# cpu-68010.net
KiCad netlist of a schematic drawn in EAGLE
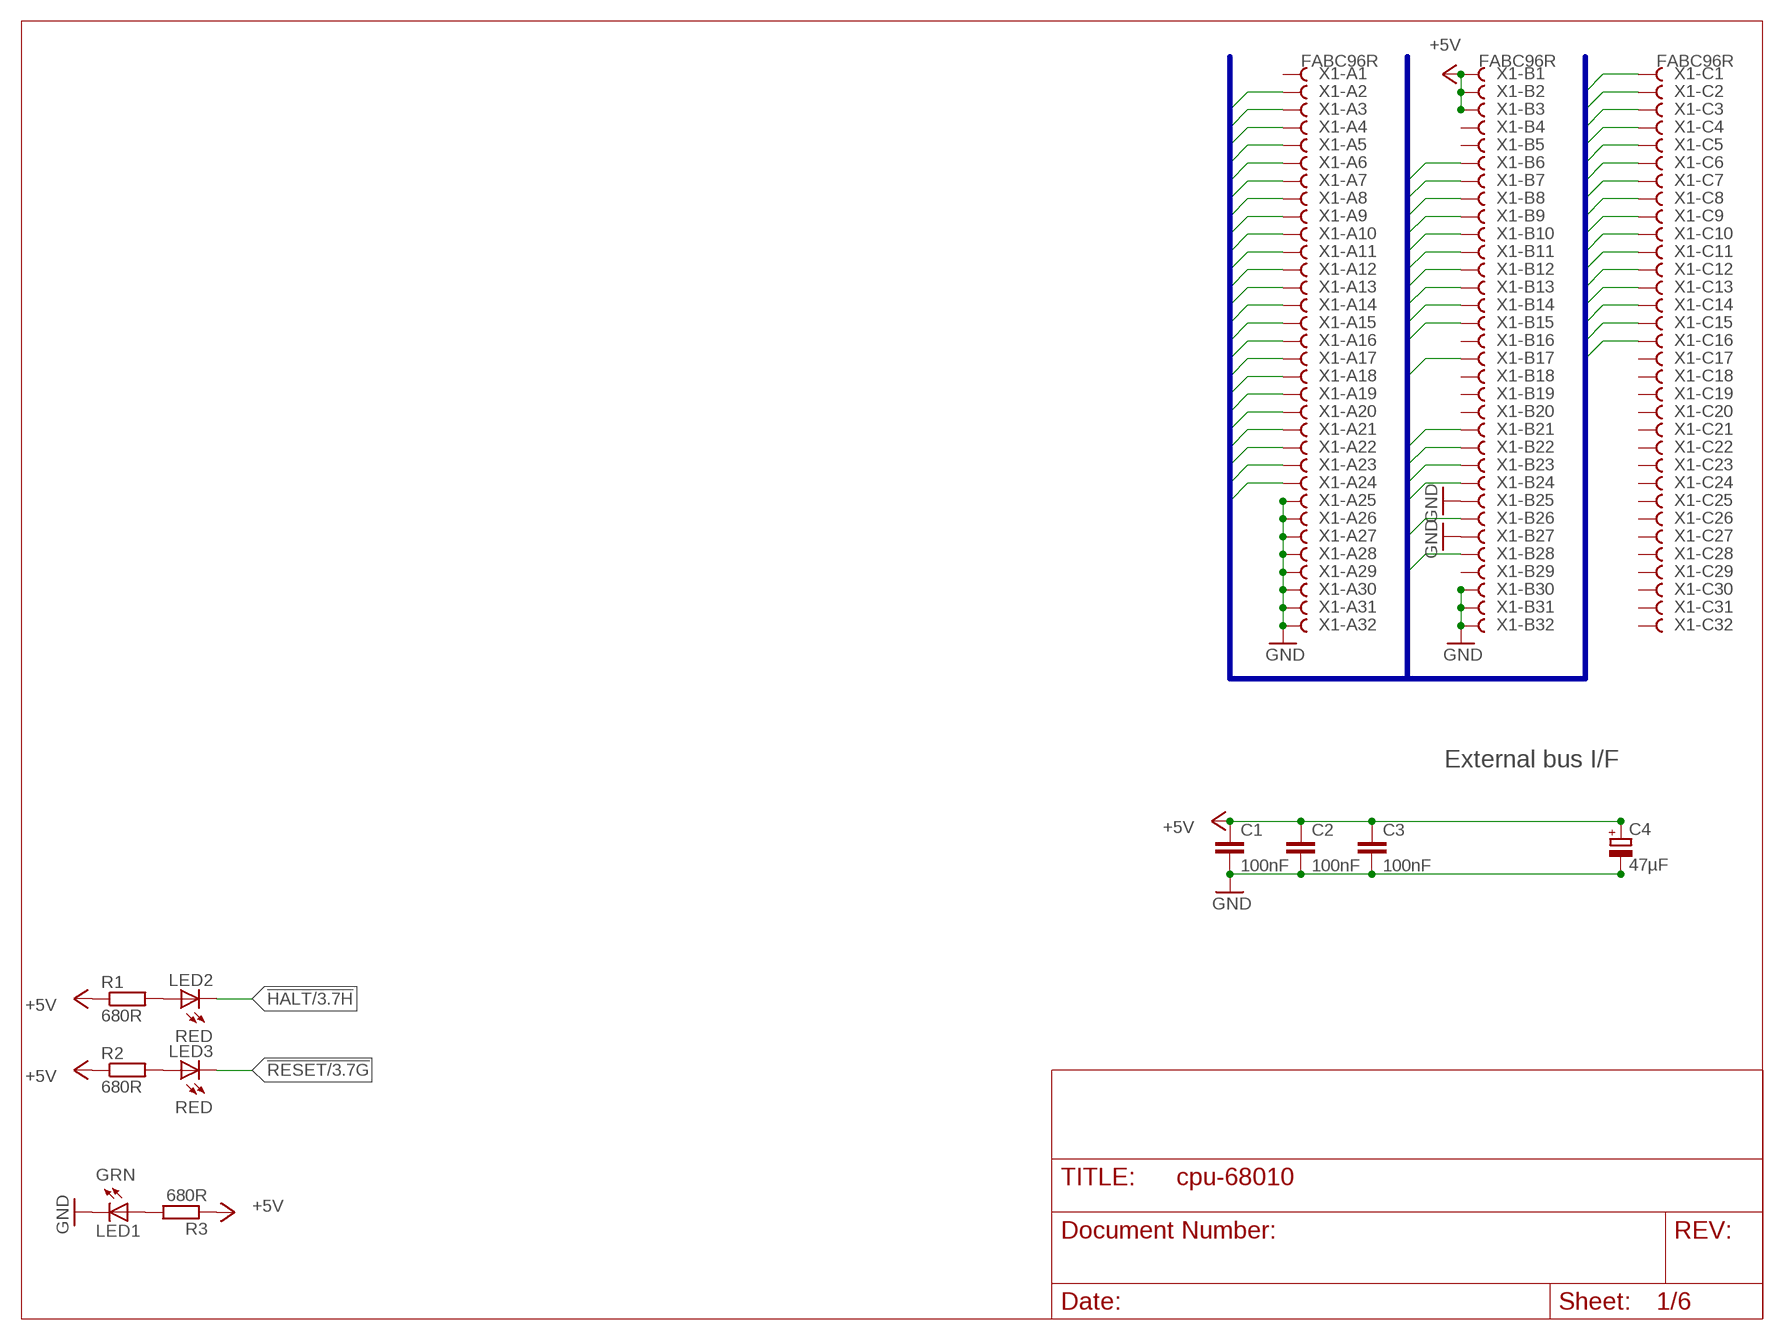
[diagram p0: schematic, sheet 1]
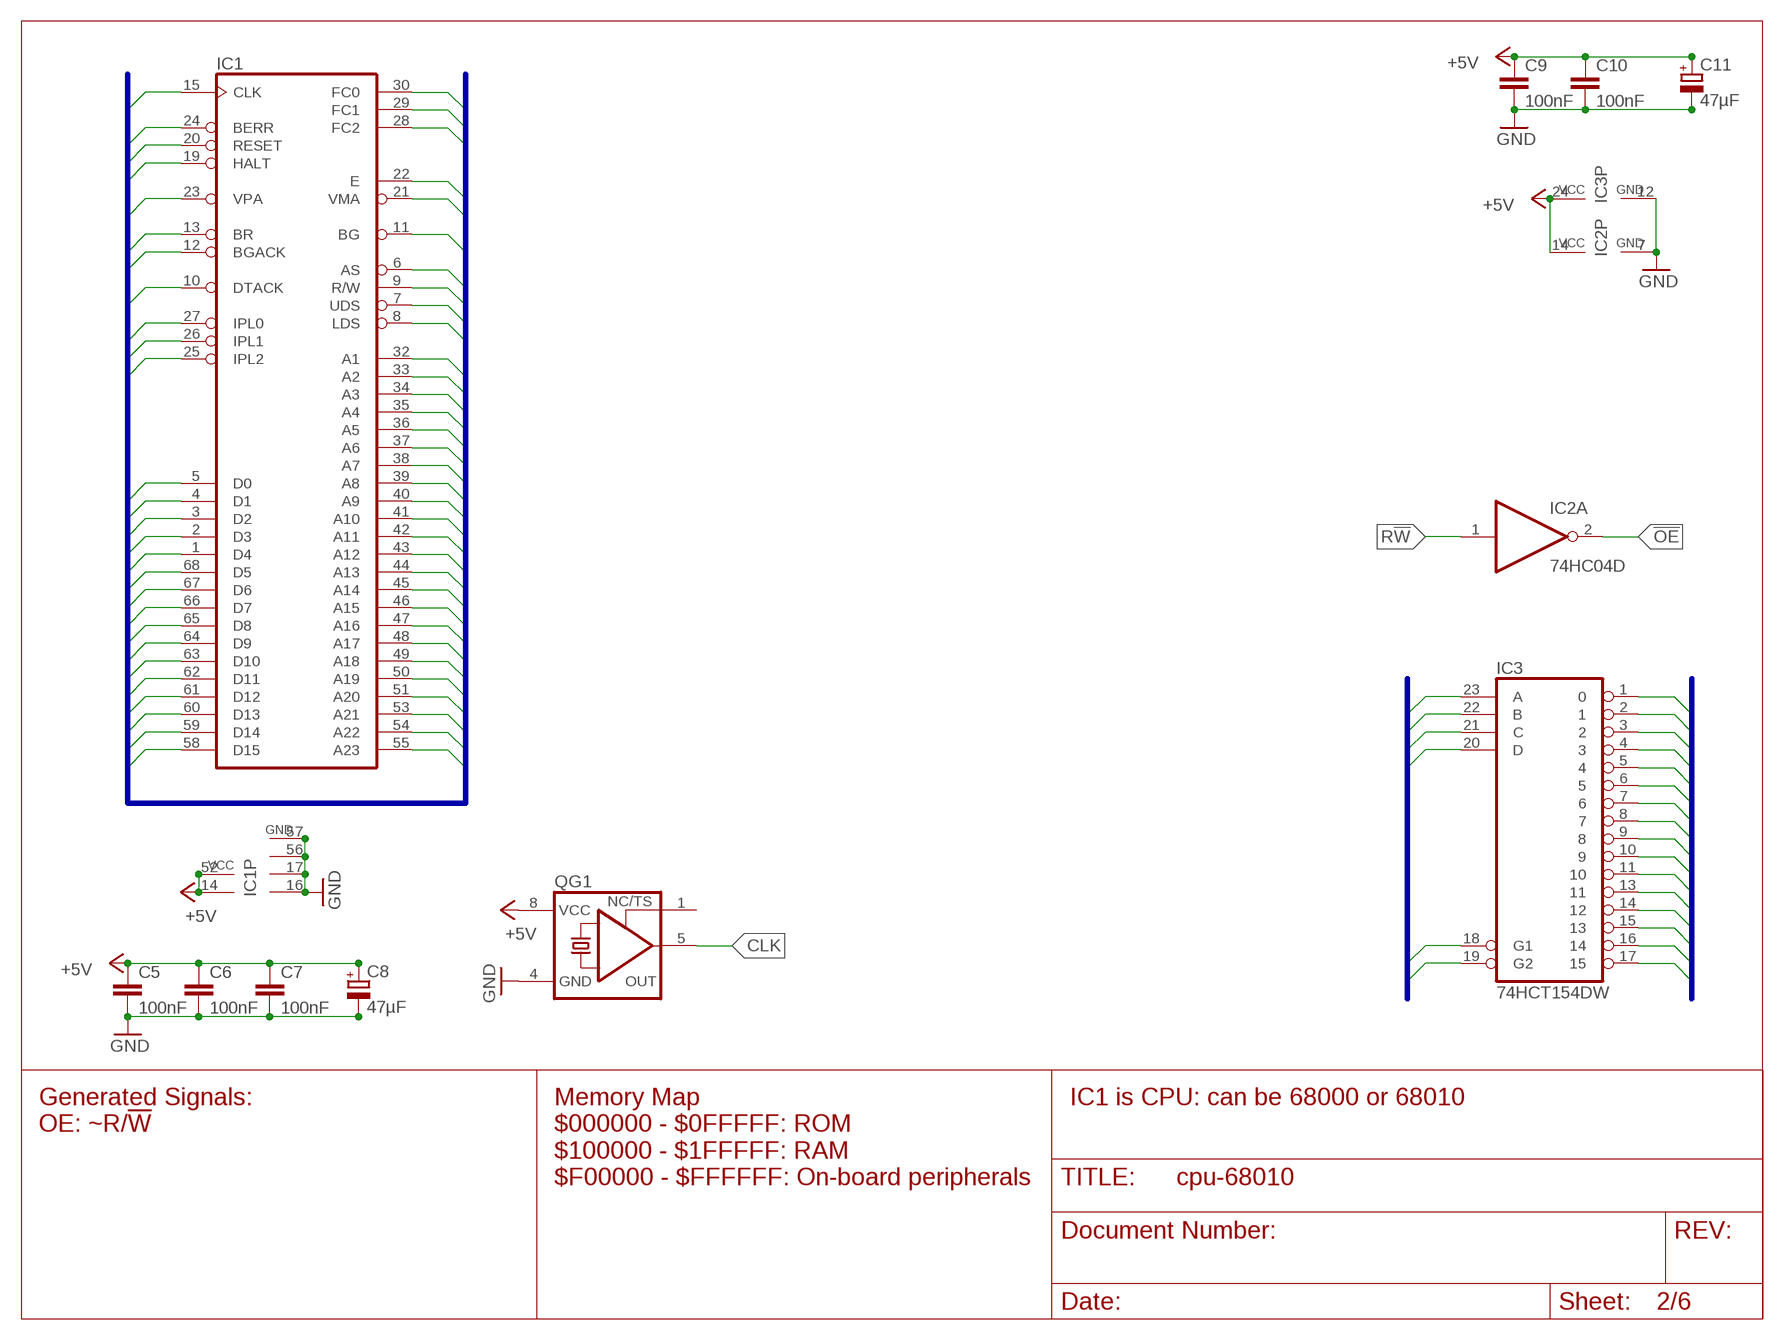
[diagram p1: schematic, sheet 2]
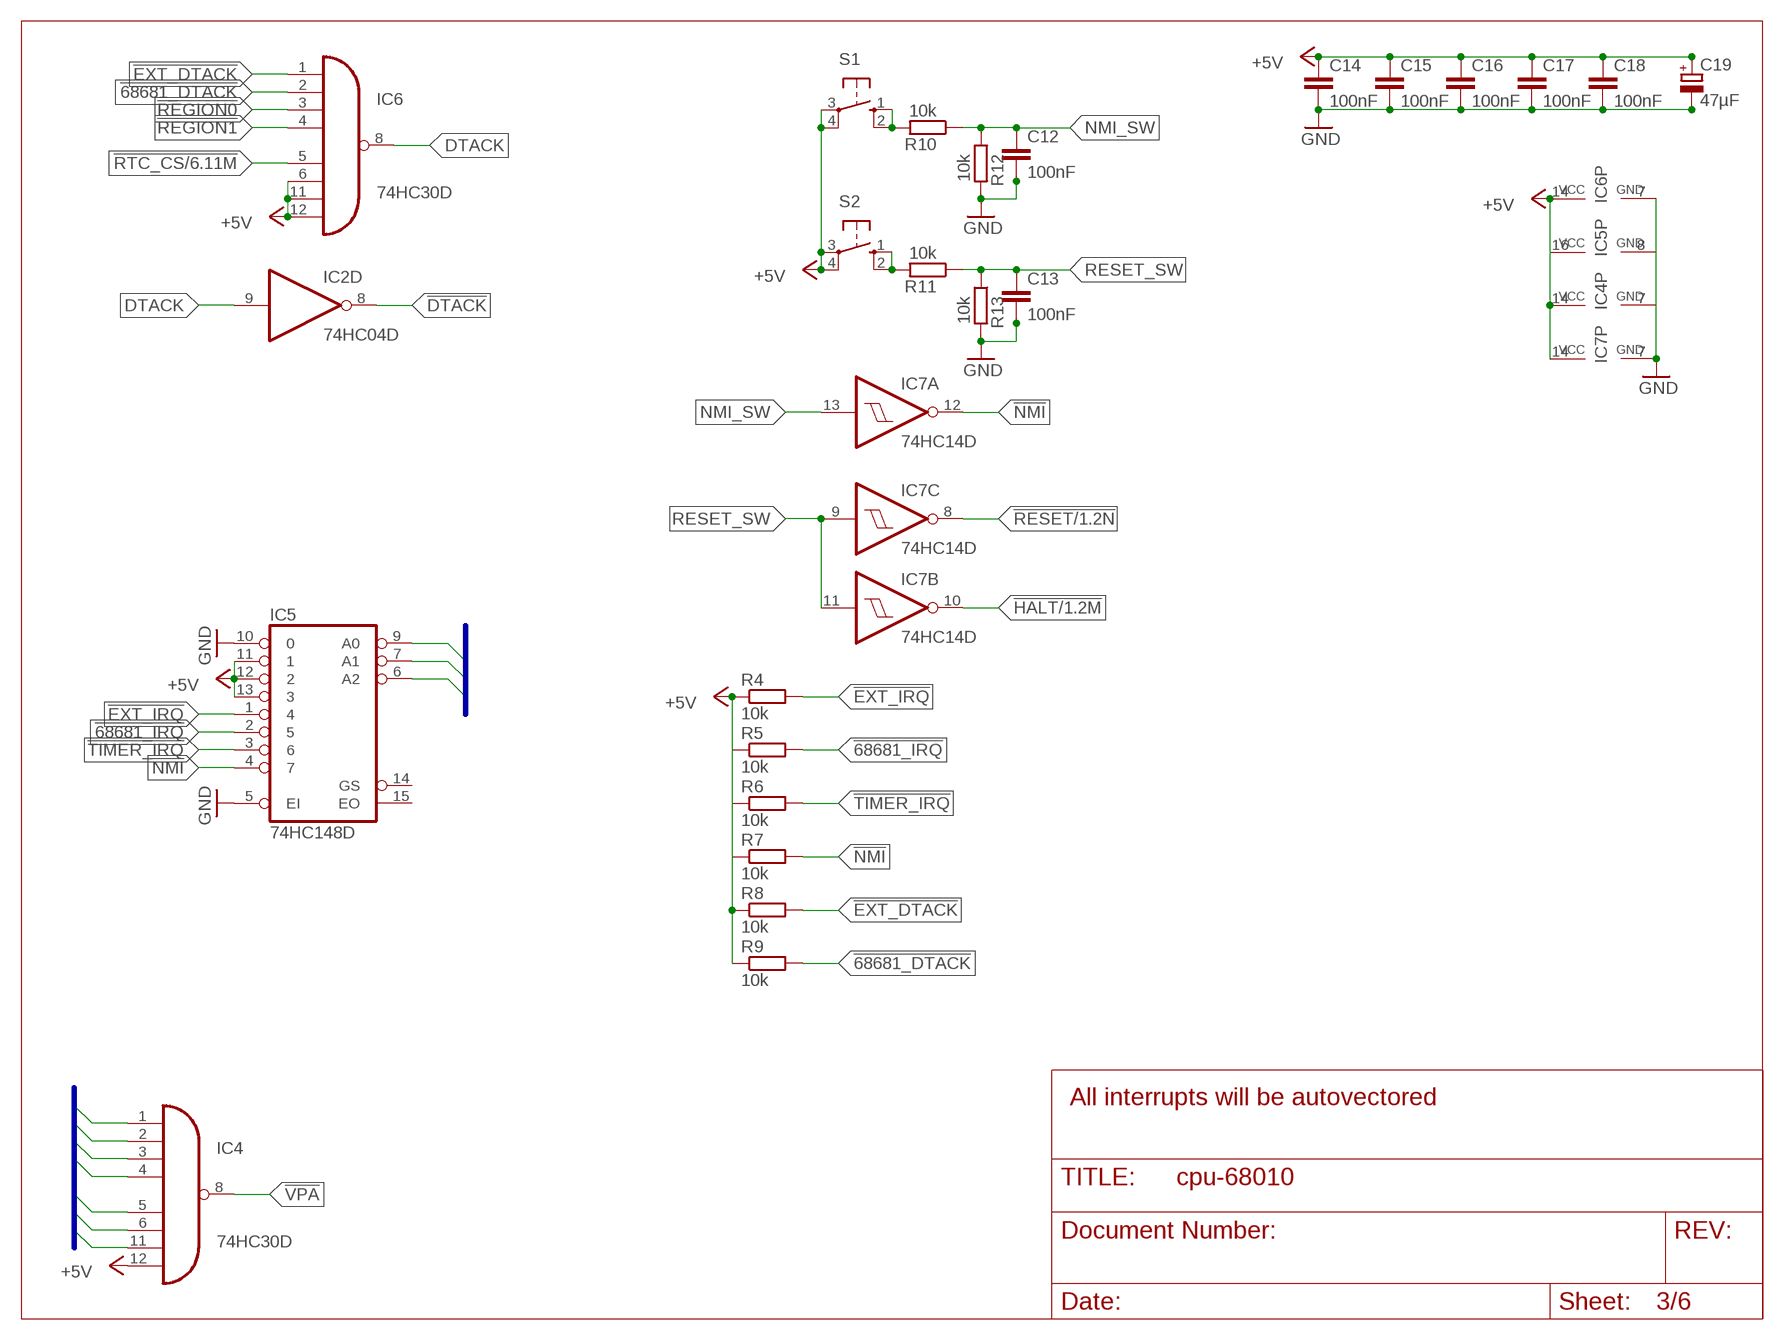
[diagram p2: schematic, sheet 3]
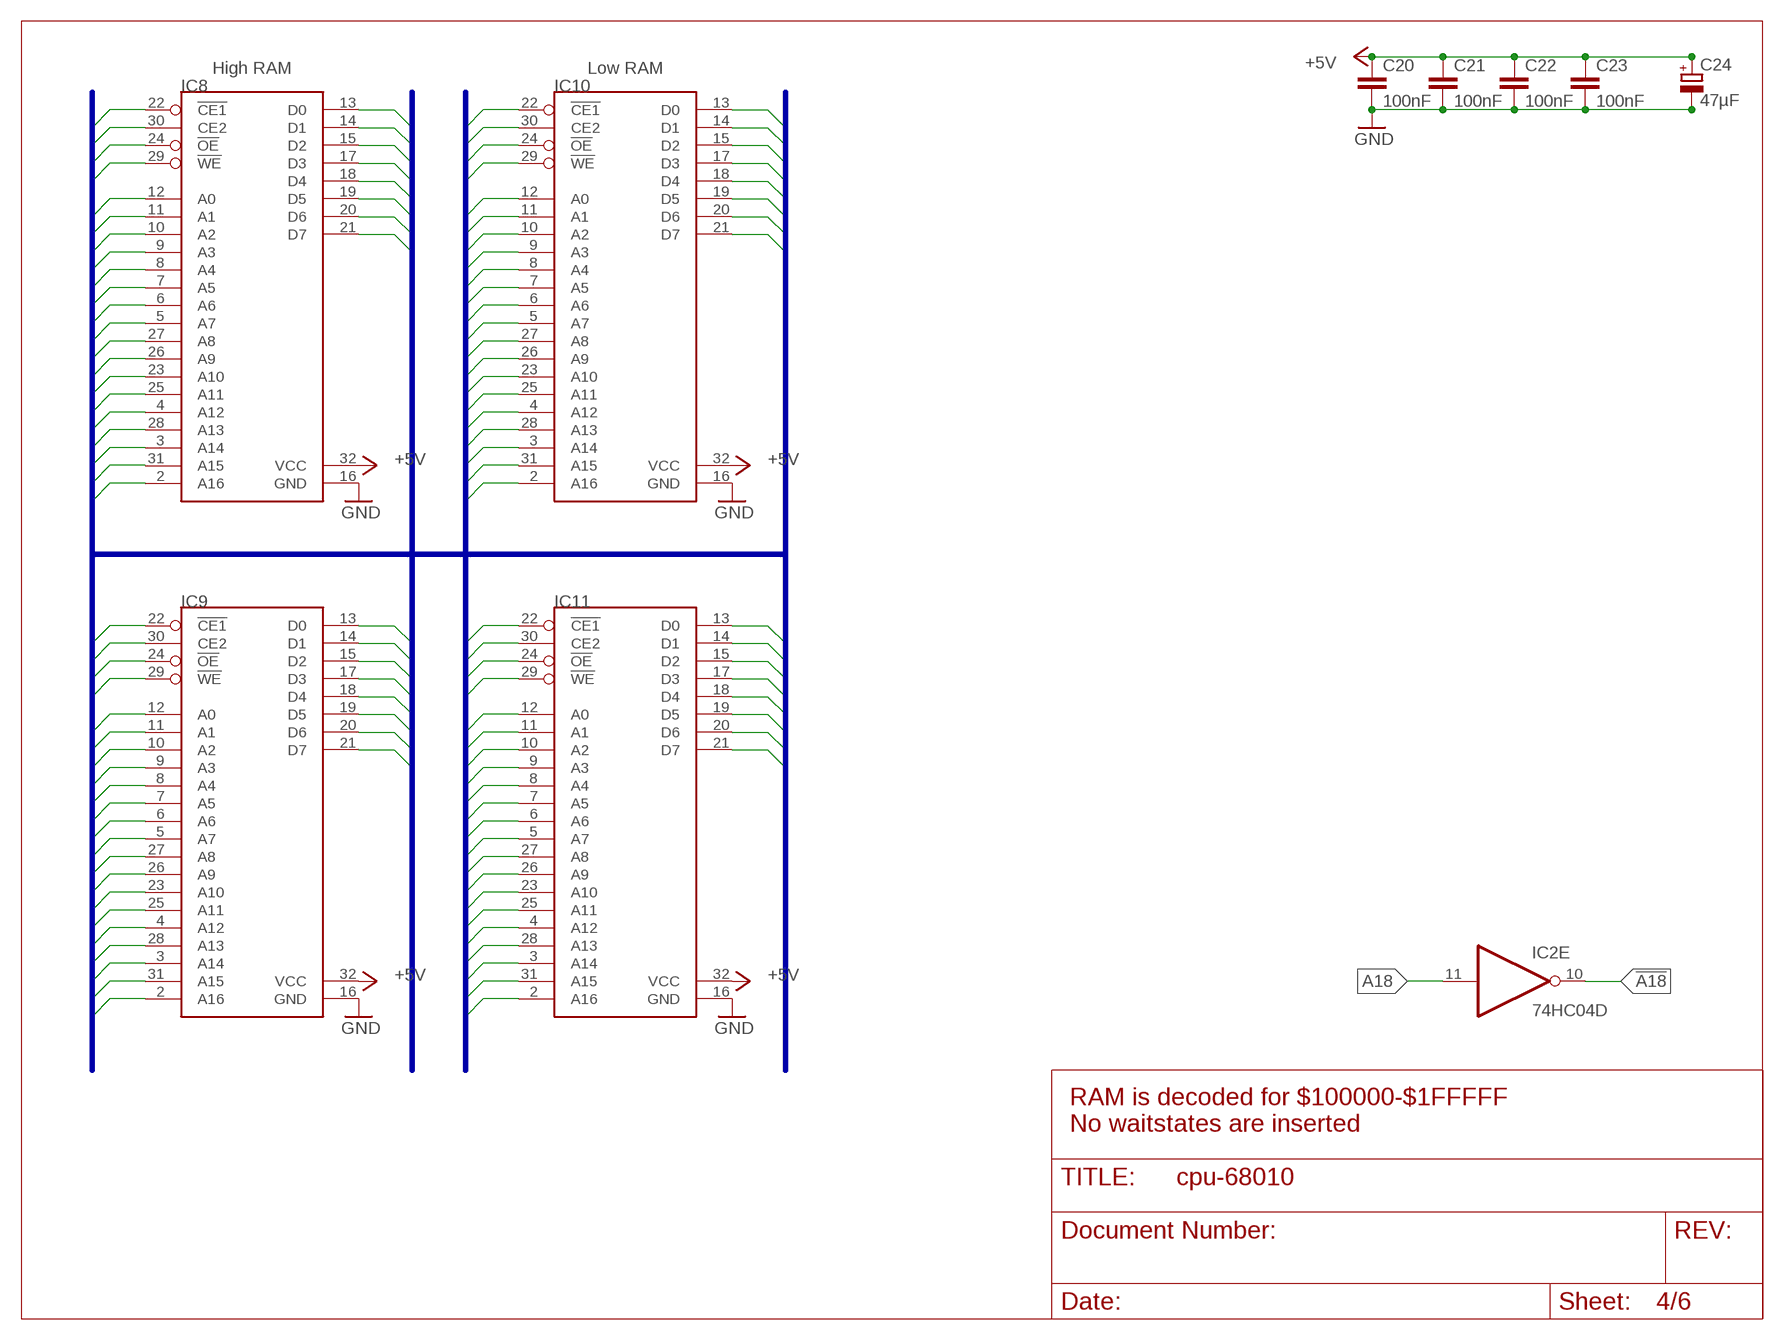
[diagram p3: schematic, sheet 4]
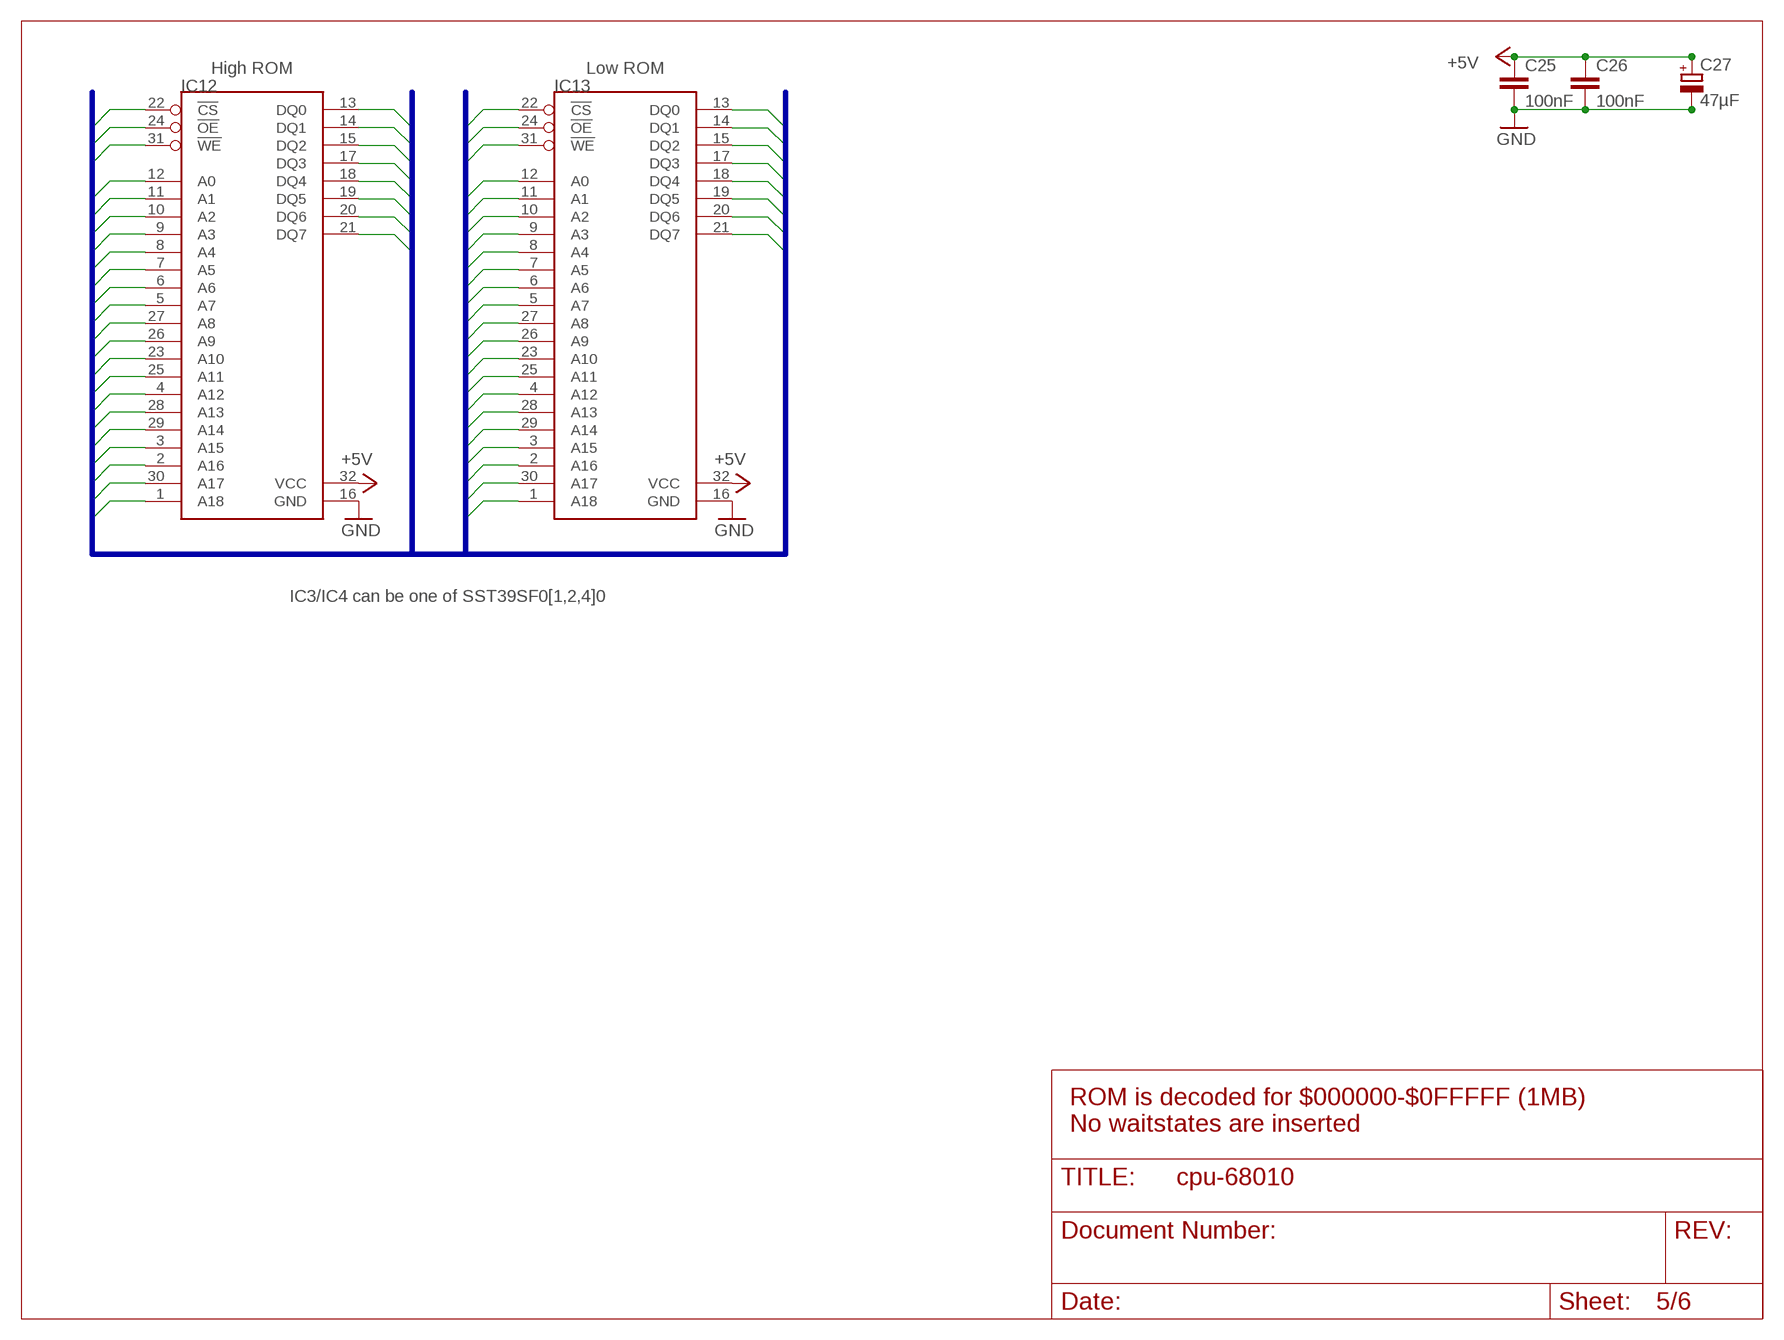
[diagram p4: schematic, sheet 5]
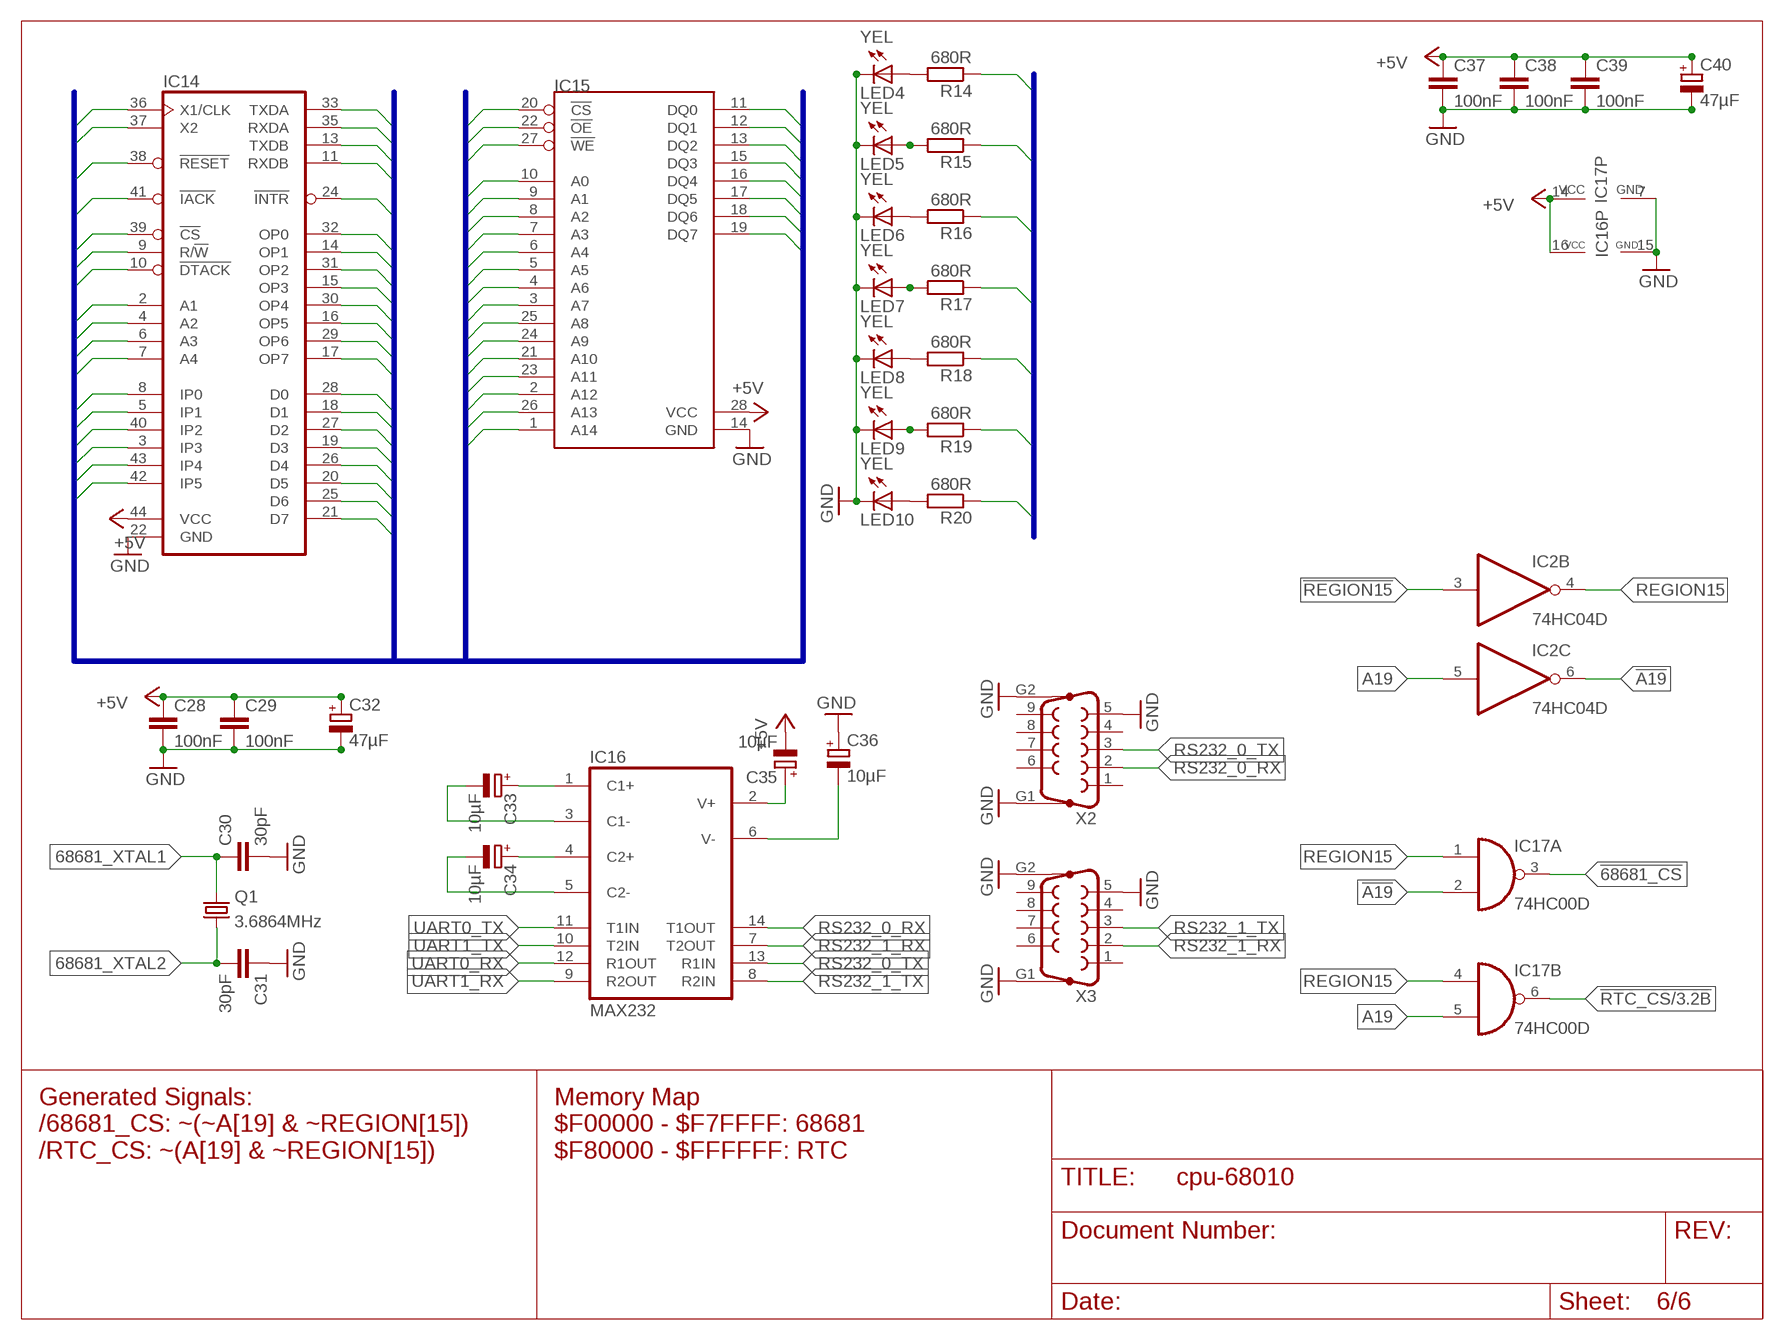
[diagram p5: schematic, sheet 6]

(export (version "E")
  (design (tool "Eeschema 10.0.6"))
  (components
    (comp (ref "C12")
      (value "100nF")
      (footprint "eagle-import:C0805")
      (libsource (lib "eagle-import") (part "C-EUC0805"))
    )
    (comp (ref "C13")
      (value "100nF")
      (footprint "eagle-import:C0805")
      (libsource (lib "eagle-import") (part "C-EUC0805"))
    )
    (comp (ref "C14")
      (value "100nF")
      (footprint "eagle-import:C0805")
      (libsource (lib "eagle-import") (part "C-EUC0805"))
    )
    (comp (ref "C15")
      (value "100nF")
      (footprint "eagle-import:C0805")
      (libsource (lib "eagle-import") (part "C-EUC0805"))
    )
    (comp (ref "C16")
      (value "100nF")
      (footprint "eagle-import:C0805")
      (libsource (lib "eagle-import") (part "C-EUC0805"))
    )
    (comp (ref "C17")
      (value "100nF")
      (footprint "eagle-import:C0805")
      (libsource (lib "eagle-import") (part "C-EUC0805"))
    )
    (comp (ref "C18")
      (value "100nF")
      (footprint "eagle-import:C0805")
      (libsource (lib "eagle-import") (part "C-EUC0805"))
    )
    (comp (ref "C19")
      (value "47µF")
      (footprint "eagle-import:CT6032")
      (libsource (lib "eagle-import") (part "CPOL-EUCT6032"))
    )
    (comp (ref "IC2")
      (value "74HC04D")
      (footprint "eagle-import:SO14")
      (libsource (lib "eagle-import") (part "7404DHC"))
    )
    (comp (ref "IC4")
      (value "74HC30D")
      (footprint "eagle-import:SO14")
      (libsource (lib "eagle-import") (part "7430DHC"))
    )
    (comp (ref "IC5")
      (value "74HC148D")
      (footprint "eagle-import:SO16")
      (libsource (lib "eagle-import") (part "74148DHC"))
    )
    (comp (ref "IC6")
      (value "74HC30D")
      (footprint "eagle-import:SO14")
      (libsource (lib "eagle-import") (part "7430DHC"))
    )
    (comp (ref "IC7")
      (value "74HC14D")
      (footprint "eagle-import:SO14")
      (libsource (lib "eagle-import") (part "7414DHC"))
    )
    (comp (ref "R4")
      (value "10k")
      (footprint "eagle-import:M0805")
      (libsource (lib "eagle-import") (part "R-EU_M0805"))
    )
    (comp (ref "R5")
      (value "10k")
      (footprint "eagle-import:M0805")
      (libsource (lib "eagle-import") (part "R-EU_M0805"))
    )
    (comp (ref "R6")
      (value "10k")
      (footprint "eagle-import:M0805")
      (libsource (lib "eagle-import") (part "R-EU_M0805"))
    )
    (comp (ref "R7")
      (value "10k")
      (footprint "eagle-import:M0805")
      (libsource (lib "eagle-import") (part "R-EU_M0805"))
    )
    (comp (ref "R8")
      (value "10k")
      (footprint "eagle-import:M0805")
      (libsource (lib "eagle-import") (part "R-EU_M0805"))
    )
    (comp (ref "R9")
      (value "10k")
      (footprint "eagle-import:M0805")
      (libsource (lib "eagle-import") (part "R-EU_M0805"))
    )
    (comp (ref "R10")
      (value "10k")
      (footprint "eagle-import:M0805")
      (libsource (lib "eagle-import") (part "R-EU_M0805"))
    )
    (comp (ref "R11")
      (value "10k")
      (footprint "eagle-import:M0805")
      (libsource (lib "eagle-import") (part "R-EU_M0805"))
    )
    (comp (ref "R12")
      (value "10k")
      (footprint "eagle-import:M0805")
      (libsource (lib "eagle-import") (part "R-EU_M0805"))
    )
    (comp (ref "R13")
      (value "10k")
      (footprint "eagle-import:M0805")
      (libsource (lib "eagle-import") (part "R-EU_M0805"))
    )
    (comp (ref "S1")
      (value "10-XX")
      (footprint "eagle-import:B3F-10XX")
      (fields (field (name "MPN") "B3F-1000"))
      (libsource (lib "eagle-import") (part "10-XX"))
    )
    (comp (ref "S2")
      (value "10-XX")
      (footprint "eagle-import:B3F-10XX")
      (fields (field (name "MPN") "B3F-1000"))
      (libsource (lib "eagle-import") (part "10-XX"))
    )
    (comp (ref "C25")
      (value "100nF")
      (footprint "eagle-import:C0805")
      (libsource (lib "eagle-import") (part "C-EUC0805"))
    )
    (comp (ref "C26")
      (value "100nF")
      (footprint "eagle-import:C0805")
      (libsource (lib "eagle-import") (part "C-EUC0805"))
    )
    (comp (ref "C27")
      (value "47µF")
      (footprint "eagle-import:CT6032")
      (libsource (lib "eagle-import") (part "CPOL-EUCT6032"))
    )
    (comp (ref "IC12")
      (value "SST39SF0X0PDIP32")
      (footprint "eagle-import:DIL32")
      (libsource (lib "eagle-import") (part "SST39SF0X0PDIP32"))
    )
    (comp (ref "IC13")
      (value "SST39SF0X0PDIP32")
      (footprint "eagle-import:DIL32")
      (libsource (lib "eagle-import") (part "SST39SF0X0PDIP32"))
    )
    (comp (ref "C5")
      (value "100nF")
      (footprint "eagle-import:C0805")
      (libsource (lib "eagle-import") (part "C-EUC0805"))
    )
    (comp (ref "C6")
      (value "100nF")
      (footprint "eagle-import:C0805")
      (libsource (lib "eagle-import") (part "C-EUC0805"))
    )
    (comp (ref "C7")
      (value "100nF")
      (footprint "eagle-import:C0805")
      (libsource (lib "eagle-import") (part "C-EUC0805"))
    )
    (comp (ref "C8")
      (value "47µF")
      (footprint "eagle-import:CT6032")
      (libsource (lib "eagle-import") (part "CPOL-EUCT6032"))
    )
    (comp (ref "C9")
      (value "100nF")
      (footprint "eagle-import:C0805")
      (libsource (lib "eagle-import") (part "C-EUC0805"))
    )
    (comp (ref "C10")
      (value "100nF")
      (footprint "eagle-import:C0805")
      (libsource (lib "eagle-import") (part "C-EUC0805"))
    )
    (comp (ref "C11")
      (value "47µF")
      (footprint "eagle-import:CT6032")
      (libsource (lib "eagle-import") (part "CPOL-EUCT6032"))
    )
    (comp (ref "IC1")
      (value "MC68000FN-SOC")
      (footprint "eagle-import:PLCC68SOCK")
      (libsource (lib "eagle-import") (part "MC68000FN-SOC"))
    )
    (comp (ref "IC3")
      (value "74HCT154DW")
      (footprint "eagle-import:SO24W")
      (libsource (lib "eagle-import") (part "74154DWHCT"))
    )
    (comp (ref "QG1")
      (value "XO-8")
      (footprint "eagle-import:DIL08S")
      (libsource (lib "eagle-import") (part "XO-8"))
    )
    (comp (ref "C28")
      (value "100nF")
      (footprint "eagle-import:C0805")
      (libsource (lib "eagle-import") (part "C-EUC0805"))
    )
    (comp (ref "C29")
      (value "100nF")
      (footprint "eagle-import:C0805")
      (libsource (lib "eagle-import") (part "C-EUC0805"))
    )
    (comp (ref "C30")
      (value "30pF")
      (footprint "eagle-import:C0805")
      (libsource (lib "eagle-import") (part "C-EUC0805"))
    )
    (comp (ref "C31")
      (value "30pF")
      (footprint "eagle-import:C0805")
      (libsource (lib "eagle-import") (part "C-EUC0805"))
    )
    (comp (ref "C32")
      (value "47µF")
      (footprint "eagle-import:CT6032")
      (libsource (lib "eagle-import") (part "CPOL-EUCT6032"))
    )
    (comp (ref "C33")
      (value "10µF")
      (footprint "eagle-import:E1,8-4")
      (libsource (lib "eagle-import") (part "CPOL-EUE1.8-4"))
    )
    (comp (ref "C34")
      (value "10µF")
      (footprint "eagle-import:E1,8-4")
      (libsource (lib "eagle-import") (part "CPOL-EUE1.8-4"))
    )
    (comp (ref "C35")
      (value "10µF")
      (footprint "eagle-import:E1,8-4")
      (libsource (lib "eagle-import") (part "CPOL-EUE1.8-4"))
    )
    (comp (ref "C36")
      (value "10µF")
      (footprint "eagle-import:E1,8-4")
      (libsource (lib "eagle-import") (part "CPOL-EUE1.8-4"))
    )
    (comp (ref "C37")
      (value "100nF")
      (footprint "eagle-import:C0805")
      (libsource (lib "eagle-import") (part "C-EUC0805"))
    )
    (comp (ref "C38")
      (value "100nF")
      (footprint "eagle-import:C0805")
      (libsource (lib "eagle-import") (part "C-EUC0805"))
    )
    (comp (ref "C39")
      (value "100nF")
      (footprint "eagle-import:C0805")
      (libsource (lib "eagle-import") (part "C-EUC0805"))
    )
    (comp (ref "C40")
      (value "47µF")
      (footprint "eagle-import:CT6032")
      (libsource (lib "eagle-import") (part "CPOL-EUCT6032"))
    )
    (comp (ref "IC14")
      (value "MC68681PLCC44-SOCKET")
      (footprint "eagle-import:PLCC-S44")
      (libsource (lib "eagle-import") (part "MC68681PLCC44-SOCKET"))
    )
    (comp (ref "IC15")
      (value "DS1244EDIP-28")
      (footprint "eagle-import:DIL28-6")
      (libsource (lib "eagle-import") (part "DS1244EDIP-28"))
    )
    (comp (ref "IC16")
      (value "MAX232")
      (footprint "eagle-import:DIL16")
      (fields (field (name "MF") "MAXIM") (field (name "MPN") "MAX232ACPE+"))
      (libsource (lib "eagle-import") (part "MAX232"))
    )
    (comp (ref "IC17")
      (value "74HC00D")
      (footprint "eagle-import:SO14")
      (libsource (lib "eagle-import") (part "7400DHC"))
    )
    (comp (ref "LED4")
      (value "YEL")
      (footprint "eagle-import:CHIPLED_1206")
      (libsource (lib "eagle-import") (part "LEDCHIPLED_1206"))
    )
    (comp (ref "LED5")
      (value "YEL")
      (footprint "eagle-import:CHIPLED_1206")
      (libsource (lib "eagle-import") (part "LEDCHIPLED_1206"))
    )
    (comp (ref "LED6")
      (value "YEL")
      (footprint "eagle-import:CHIPLED_1206")
      (libsource (lib "eagle-import") (part "LEDCHIPLED_1206"))
    )
    (comp (ref "LED7")
      (value "YEL")
      (footprint "eagle-import:CHIPLED_1206")
      (libsource (lib "eagle-import") (part "LEDCHIPLED_1206"))
    )
    (comp (ref "LED8")
      (value "YEL")
      (footprint "eagle-import:CHIPLED_1206")
      (libsource (lib "eagle-import") (part "LEDCHIPLED_1206"))
    )
    (comp (ref "LED9")
      (value "YEL")
      (footprint "eagle-import:CHIPLED_1206")
      (libsource (lib "eagle-import") (part "LEDCHIPLED_1206"))
    )
    (comp (ref "LED10")
      (value "YEL")
      (footprint "eagle-import:CHIPLED_1206")
      (libsource (lib "eagle-import") (part "LEDCHIPLED_1206"))
    )
    (comp (ref "Q1")
      (value "3.6864MHz")
      (footprint "eagle-import:HC49_S")
      (libsource (lib "eagle-import") (part "CRYSTALHC49S"))
    )
    (comp (ref "R14")
      (value "680R")
      (footprint "eagle-import:M0805")
      (libsource (lib "eagle-import") (part "R-EU_M0805"))
    )
    (comp (ref "R15")
      (value "680R")
      (footprint "eagle-import:M0805")
      (libsource (lib "eagle-import") (part "R-EU_M0805"))
    )
    (comp (ref "R16")
      (value "680R")
      (footprint "eagle-import:M0805")
      (libsource (lib "eagle-import") (part "R-EU_M0805"))
    )
    (comp (ref "R17")
      (value "680R")
      (footprint "eagle-import:M0805")
      (libsource (lib "eagle-import") (part "R-EU_M0805"))
    )
    (comp (ref "R18")
      (value "680R")
      (footprint "eagle-import:M0805")
      (libsource (lib "eagle-import") (part "R-EU_M0805"))
    )
    (comp (ref "R19")
      (value "680R")
      (footprint "eagle-import:M0805")
      (libsource (lib "eagle-import") (part "R-EU_M0805"))
    )
    (comp (ref "R20")
      (value "680R")
      (footprint "eagle-import:M0805")
      (libsource (lib "eagle-import") (part "R-EU_M0805"))
    )
    (comp (ref "X2")
      (value "F09HP")
      (footprint "eagle-import:F09HP")
      (libsource (lib "eagle-import") (part "F09HP"))
    )
    (comp (ref "X3")
      (value "F09HP")
      (footprint "eagle-import:F09HP")
      (libsource (lib "eagle-import") (part "F09HP"))
    )
    (comp (ref "C20")
      (value "100nF")
      (footprint "eagle-import:C0805")
      (libsource (lib "eagle-import") (part "C-EUC0805"))
    )
    (comp (ref "C21")
      (value "100nF")
      (footprint "eagle-import:C0805")
      (libsource (lib "eagle-import") (part "C-EUC0805"))
    )
    (comp (ref "C22")
      (value "100nF")
      (footprint "eagle-import:C0805")
      (libsource (lib "eagle-import") (part "C-EUC0805"))
    )
    (comp (ref "C23")
      (value "100nF")
      (footprint "eagle-import:C0805")
      (libsource (lib "eagle-import") (part "C-EUC0805"))
    )
    (comp (ref "C24")
      (value "47µF")
      (footprint "eagle-import:CT6032")
      (libsource (lib "eagle-import") (part "CPOL-EUCT6032"))
    )
    (comp (ref "IC8")
      (value "CY62128BSOIC32")
      (footprint "eagle-import:SO32X")
      (libsource (lib "eagle-import") (part "CY62128BSOIC32"))
    )
    (comp (ref "IC9")
      (value "CY62128BSOIC32")
      (footprint "eagle-import:SO32X")
      (libsource (lib "eagle-import") (part "CY62128BSOIC32"))
    )
    (comp (ref "IC10")
      (value "CY62128BSOIC32")
      (footprint "eagle-import:SO32X")
      (libsource (lib "eagle-import") (part "CY62128BSOIC32"))
    )
    (comp (ref "IC11")
      (value "CY62128BSOIC32")
      (footprint "eagle-import:SO32X")
      (libsource (lib "eagle-import") (part "CY62128BSOIC32"))
    )
    (comp (ref "C1")
      (value "100nF")
      (footprint "eagle-import:C0805")
      (libsource (lib "eagle-import") (part "C-EUC0805"))
    )
    (comp (ref "C2")
      (value "100nF")
      (footprint "eagle-import:C0805")
      (libsource (lib "eagle-import") (part "C-EUC0805"))
    )
    (comp (ref "C3")
      (value "100nF")
      (footprint "eagle-import:C0805")
      (libsource (lib "eagle-import") (part "C-EUC0805"))
    )
    (comp (ref "C4")
      (value "47µF")
      (footprint "eagle-import:CT6032")
      (libsource (lib "eagle-import") (part "CPOL-EUCT6032"))
    )
    (comp (ref "LED1")
      (value "GRN")
      (footprint "eagle-import:CHIPLED_1206")
      (libsource (lib "eagle-import") (part "LEDCHIPLED_1206"))
    )
    (comp (ref "LED2")
      (value "RED")
      (footprint "eagle-import:CHIPLED_1206")
      (libsource (lib "eagle-import") (part "LEDCHIPLED_1206"))
    )
    (comp (ref "LED3")
      (value "RED")
      (footprint "eagle-import:CHIPLED_1206")
      (libsource (lib "eagle-import") (part "LEDCHIPLED_1206"))
    )
    (comp (ref "R1")
      (value "680R")
      (footprint "eagle-import:M0805")
      (libsource (lib "eagle-import") (part "R-EU_M0805"))
    )
    (comp (ref "R2")
      (value "680R")
      (footprint "eagle-import:M0805")
      (libsource (lib "eagle-import") (part "R-EU_M0805"))
    )
    (comp (ref "R3")
      (value "680R")
      (footprint "eagle-import:M0805")
      (libsource (lib "eagle-import") (part "R-EU_M0805"))
    )
    (comp (ref "X1")
      (value "FABC96R")
      (footprint "eagle-import:FABC96R")
      (libsource (lib "eagle-import") (part "FABC96R"))
    )
  )
  (nets
    (net (code "1") (name "+5V") (class "Default")
      (node (ref "C1") (pin "1") (pinfunction "1_1") (pintype "passive"))
      (node (ref "C10") (pin "1") (pinfunction "1_1") (pintype "passive"))
      (node (ref "C11") (pin "+") (pinfunction "+_+") (pintype "passive"))
      (node (ref "C14") (pin "1") (pinfunction "1_1") (pintype "passive"))
      (node (ref "C15") (pin "1") (pinfunction "1_1") (pintype "passive"))
      (node (ref "C16") (pin "1") (pinfunction "1_1") (pintype "passive"))
      (node (ref "C17") (pin "1") (pinfunction "1_1") (pintype "passive"))
      (node (ref "C18") (pin "1") (pinfunction "1_1") (pintype "passive"))
      (node (ref "C19") (pin "+") (pinfunction "+_+") (pintype "passive"))
      (node (ref "C2") (pin "1") (pinfunction "1_1") (pintype "passive"))
      (node (ref "C20") (pin "1") (pinfunction "1_1") (pintype "passive"))
      (node (ref "C21") (pin "1") (pinfunction "1_1") (pintype "passive"))
      (node (ref "C22") (pin "1") (pinfunction "1_1") (pintype "passive"))
      (node (ref "C23") (pin "1") (pinfunction "1_1") (pintype "passive"))
      (node (ref "C24") (pin "+") (pinfunction "+_+") (pintype "passive"))
      (node (ref "C25") (pin "1") (pinfunction "1_1") (pintype "passive"))
      (node (ref "C26") (pin "1") (pinfunction "1_1") (pintype "passive"))
      (node (ref "C27") (pin "+") (pinfunction "+_+") (pintype "passive"))
      (node (ref "C28") (pin "1") (pinfunction "1_1") (pintype "passive"))
      (node (ref "C29") (pin "1") (pinfunction "1_1") (pintype "passive"))
      (node (ref "C3") (pin "1") (pinfunction "1_1") (pintype "passive"))
      (node (ref "C32") (pin "+") (pinfunction "+_+") (pintype "passive"))
      (node (ref "C35") (pin "-") (pinfunction "-_-") (pintype "passive"))
      (node (ref "C37") (pin "1") (pinfunction "1_1") (pintype "passive"))
      (node (ref "C38") (pin "1") (pinfunction "1_1") (pintype "passive"))
      (node (ref "C39") (pin "1") (pinfunction "1_1") (pintype "passive"))
      (node (ref "C4") (pin "+") (pinfunction "+_+") (pintype "passive"))
      (node (ref "C40") (pin "+") (pinfunction "+_+") (pintype "passive"))
      (node (ref "C5") (pin "1") (pinfunction "1_1") (pintype "passive"))
      (node (ref "C6") (pin "1") (pinfunction "1_1") (pintype "passive"))
      (node (ref "C7") (pin "1") (pinfunction "1_1") (pintype "passive"))
      (node (ref "C8") (pin "+") (pinfunction "+_+") (pintype "passive"))
      (node (ref "C9") (pin "1") (pinfunction "1_1") (pintype "passive"))
      (node (ref "IC1") (pin "14") (pinfunction "VCC_14") (pintype "power_in"))
      (node (ref "IC1") (pin "52") (pinfunction "VCC_52") (pintype "power_in"))
      (node (ref "IC10") (pin "32") (pinfunction "VCC_32") (pintype "power_in"))
      (node (ref "IC11") (pin "32") (pinfunction "VCC_32") (pintype "power_in"))
      (node (ref "IC12") (pin "32") (pinfunction "VCC_32") (pintype "power_in"))
      (node (ref "IC13") (pin "32") (pinfunction "VCC_32") (pintype "power_in"))
      (node (ref "IC14") (pin "44") (pinfunction "VCC_44") (pintype "power_in"))
      (node (ref "IC15") (pin "28") (pinfunction "VCC_28") (pintype "power_in"))
      (node (ref "IC16") (pin "16") (pinfunction "VCC_16") (pintype "power_in"))
      (node (ref "IC17") (pin "14") (pinfunction "VCC_14") (pintype "power_in"))
      (node (ref "IC2") (pin "14") (pinfunction "VCC_14") (pintype "power_in"))
      (node (ref "IC3") (pin "24") (pinfunction "VCC_24") (pintype "power_in"))
      (node (ref "IC4") (pin "12") (pinfunction "I7_12") (pintype "input"))
      (node (ref "IC4") (pin "14") (pinfunction "VCC_14") (pintype "power_in"))
      (node (ref "IC5") (pin "11") (pinfunction "1_11") (pintype "input"))
      (node (ref "IC5") (pin "12") (pinfunction "2_12") (pintype "input"))
      (node (ref "IC5") (pin "13") (pinfunction "3_13") (pintype "input"))
      (node (ref "IC5") (pin "16") (pinfunction "VCC_16") (pintype "power_in"))
      (node (ref "IC6") (pin "11") (pinfunction "I6_11") (pintype "input"))
      (node (ref "IC6") (pin "12") (pinfunction "I7_12") (pintype "input"))
      (node (ref "IC6") (pin "14") (pinfunction "VCC_14") (pintype "power_in"))
      (node (ref "IC6") (pin "6") (pinfunction "I5_6") (pintype "input"))
      (node (ref "IC7") (pin "14") (pinfunction "VCC_14") (pintype "power_in"))
      (node (ref "IC8") (pin "32") (pinfunction "VCC_32") (pintype "power_in"))
      (node (ref "IC9") (pin "32") (pinfunction "VCC_32") (pintype "power_in"))
      (node (ref "QG1") (pin "8") (pinfunction "VCC_8") (pintype "power_in"))
      (node (ref "R1") (pin "1") (pinfunction "1_1") (pintype "passive"))
      (node (ref "R2") (pin "1") (pinfunction "1_1") (pintype "passive"))
      (node (ref "R3") (pin "1") (pinfunction "1_1") (pintype "passive"))
      (node (ref "R4") (pin "1") (pinfunction "1_1") (pintype "passive"))
      (node (ref "R8") (pin "1") (pinfunction "1_1") (pintype "passive"))
      (node (ref "R9") (pin "1") (pinfunction "1_1") (pintype "passive"))
      (node (ref "S1") (pin "3") (pinfunction "P_3") (pintype "passive"))
      (node (ref "S1") (pin "4") (pinfunction "P1_4") (pintype "passive"))
      (node (ref "S2") (pin "3") (pinfunction "P_3") (pintype "passive"))
      (node (ref "S2") (pin "4") (pinfunction "P1_4") (pintype "passive"))
      (node (ref "X1") (pin "B1") (pinfunction "B_B1") (pintype "passive"))
      (node (ref "X1") (pin "B2") (pinfunction "B_B2") (pintype "passive"))
      (node (ref "X1") (pin "B3") (pinfunction "B_B3") (pintype "passive"))
    )
    (net (code "3") (name "68681_XTAL1") (class "Default")
      (node (ref "C30") (pin "1") (pinfunction "1_1") (pintype "passive"))
      (node (ref "IC14") (pin "36") (pinfunction "X1/CLK_36") (pintype "input"))
      (node (ref "Q1") (pin "2") (pinfunction "2_2") (pintype "passive"))
    )
    (net (code "4") (name "68681_XTAL2") (class "Default")
      (node (ref "C31") (pin "2") (pinfunction "2_2") (pintype "passive"))
      (node (ref "IC14") (pin "37") (pinfunction "X2_37") (pintype "output"))
      (node (ref "Q1") (pin "1") (pinfunction "1_1") (pintype "passive"))
    )
    (net (code "5") (name "A1") (class "Default")
      (node (ref "IC1") (pin "32") (pinfunction "A1_32") (pintype "output"))
      (node (ref "IC10") (pin "12") (pinfunction "A0_12") (pintype "input"))
      (node (ref "IC11") (pin "12") (pinfunction "A0_12") (pintype "input"))
      (node (ref "IC12") (pin "12") (pinfunction "A0_12") (pintype "input"))
      (node (ref "IC13") (pin "12") (pinfunction "A0_12") (pintype "input"))
      (node (ref "IC14") (pin "2") (pinfunction "A1_2") (pintype "input"))
      (node (ref "IC15") (pin "10") (pinfunction "A0_10") (pintype "input"))
      (node (ref "IC8") (pin "12") (pinfunction "A0_12") (pintype "input"))
      (node (ref "IC9") (pin "12") (pinfunction "A0_12") (pintype "input"))
      (node (ref "X1") (pin "A2") (pinfunction "B_A2") (pintype "passive"))
    )
    (net (code "6") (name "A2") (class "Default")
      (node (ref "IC1") (pin "33") (pinfunction "A2_33") (pintype "output"))
      (node (ref "IC10") (pin "11") (pinfunction "A1_11") (pintype "input"))
      (node (ref "IC11") (pin "11") (pinfunction "A1_11") (pintype "input"))
      (node (ref "IC12") (pin "11") (pinfunction "A1_11") (pintype "input"))
      (node (ref "IC13") (pin "11") (pinfunction "A1_11") (pintype "input"))
      (node (ref "IC14") (pin "4") (pinfunction "A2_4") (pintype "input"))
      (node (ref "IC15") (pin "9") (pinfunction "A1_9") (pintype "input"))
      (node (ref "IC8") (pin "11") (pinfunction "A1_11") (pintype "input"))
      (node (ref "IC9") (pin "11") (pinfunction "A1_11") (pintype "input"))
      (node (ref "X1") (pin "A3") (pinfunction "B_A3") (pintype "passive"))
    )
    (net (code "7") (name "A3") (class "Default")
      (node (ref "IC1") (pin "34") (pinfunction "A3_34") (pintype "output"))
      (node (ref "IC10") (pin "10") (pinfunction "A2_10") (pintype "input"))
      (node (ref "IC11") (pin "10") (pinfunction "A2_10") (pintype "input"))
      (node (ref "IC12") (pin "10") (pinfunction "A2_10") (pintype "input"))
      (node (ref "IC13") (pin "10") (pinfunction "A2_10") (pintype "input"))
      (node (ref "IC14") (pin "6") (pinfunction "A3_6") (pintype "input"))
      (node (ref "IC15") (pin "8") (pinfunction "A2_8") (pintype "input"))
      (node (ref "IC8") (pin "10") (pinfunction "A2_10") (pintype "input"))
      (node (ref "IC9") (pin "10") (pinfunction "A2_10") (pintype "input"))
      (node (ref "X1") (pin "A4") (pinfunction "B_A4") (pintype "passive"))
    )
    (net (code "8") (name "A4") (class "Default")
      (node (ref "IC1") (pin "35") (pinfunction "A4_35") (pintype "output"))
      (node (ref "IC10") (pin "9") (pinfunction "A3_9") (pintype "input"))
      (node (ref "IC11") (pin "9") (pinfunction "A3_9") (pintype "input"))
      (node (ref "IC12") (pin "9") (pinfunction "A3_9") (pintype "input"))
      (node (ref "IC13") (pin "9") (pinfunction "A3_9") (pintype "input"))
      (node (ref "IC14") (pin "7") (pinfunction "A4_7") (pintype "input"))
      (node (ref "IC15") (pin "7") (pinfunction "A3_7") (pintype "input"))
      (node (ref "IC8") (pin "9") (pinfunction "A3_9") (pintype "input"))
      (node (ref "IC9") (pin "9") (pinfunction "A3_9") (pintype "input"))
      (node (ref "X1") (pin "A5") (pinfunction "B_A5") (pintype "passive"))
    )
    (net (code "9") (name "A5") (class "Default")
      (node (ref "IC1") (pin "36") (pinfunction "A5_36") (pintype "output"))
      (node (ref "IC10") (pin "8") (pinfunction "A4_8") (pintype "input"))
      (node (ref "IC11") (pin "8") (pinfunction "A4_8") (pintype "input"))
      (node (ref "IC12") (pin "8") (pinfunction "A4_8") (pintype "input"))
      (node (ref "IC13") (pin "8") (pinfunction "A4_8") (pintype "input"))
      (node (ref "IC15") (pin "6") (pinfunction "A4_6") (pintype "input"))
      (node (ref "IC8") (pin "8") (pinfunction "A4_8") (pintype "input"))
      (node (ref "IC9") (pin "8") (pinfunction "A4_8") (pintype "input"))
      (node (ref "X1") (pin "A6") (pinfunction "B_A6") (pintype "passive"))
    )
    (net (code "10") (name "A6") (class "Default")
      (node (ref "IC1") (pin "37") (pinfunction "A6_37") (pintype "output"))
      (node (ref "IC10") (pin "7") (pinfunction "A5_7") (pintype "input"))
      (node (ref "IC11") (pin "7") (pinfunction "A5_7") (pintype "input"))
      (node (ref "IC12") (pin "7") (pinfunction "A5_7") (pintype "input"))
      (node (ref "IC13") (pin "7") (pinfunction "A5_7") (pintype "input"))
      (node (ref "IC15") (pin "5") (pinfunction "A5_5") (pintype "input"))
      (node (ref "IC8") (pin "7") (pinfunction "A5_7") (pintype "input"))
      (node (ref "IC9") (pin "7") (pinfunction "A5_7") (pintype "input"))
      (node (ref "X1") (pin "A7") (pinfunction "B_A7") (pintype "passive"))
    )
    (net (code "11") (name "A7") (class "Default")
      (node (ref "IC1") (pin "38") (pinfunction "A7_38") (pintype "output"))
      (node (ref "IC10") (pin "6") (pinfunction "A6_6") (pintype "input"))
      (node (ref "IC11") (pin "6") (pinfunction "A6_6") (pintype "input"))
      (node (ref "IC12") (pin "6") (pinfunction "A6_6") (pintype "input"))
      (node (ref "IC13") (pin "6") (pinfunction "A6_6") (pintype "input"))
      (node (ref "IC15") (pin "4") (pinfunction "A6_4") (pintype "input"))
      (node (ref "IC8") (pin "6") (pinfunction "A6_6") (pintype "input"))
      (node (ref "IC9") (pin "6") (pinfunction "A6_6") (pintype "input"))
      (node (ref "X1") (pin "A8") (pinfunction "B_A8") (pintype "passive"))
    )
    (net (code "12") (name "A8") (class "Default")
      (node (ref "IC1") (pin "39") (pinfunction "A8_39") (pintype "output"))
      (node (ref "IC10") (pin "5") (pinfunction "A7_5") (pintype "input"))
      (node (ref "IC11") (pin "5") (pinfunction "A7_5") (pintype "input"))
      (node (ref "IC12") (pin "5") (pinfunction "A7_5") (pintype "input"))
      (node (ref "IC13") (pin "5") (pinfunction "A7_5") (pintype "input"))
      (node (ref "IC15") (pin "3") (pinfunction "A7_3") (pintype "input"))
      (node (ref "IC8") (pin "5") (pinfunction "A7_5") (pintype "input"))
      (node (ref "IC9") (pin "5") (pinfunction "A7_5") (pintype "input"))
      (node (ref "X1") (pin "A9") (pinfunction "B_A9") (pintype "passive"))
    )
    (net (code "13") (name "A9") (class "Default")
      (node (ref "IC1") (pin "40") (pinfunction "A9_40") (pintype "output"))
      (node (ref "IC10") (pin "27") (pinfunction "A8_27") (pintype "input"))
      (node (ref "IC11") (pin "27") (pinfunction "A8_27") (pintype "input"))
      (node (ref "IC12") (pin "27") (pinfunction "A8_27") (pintype "input"))
      (node (ref "IC13") (pin "27") (pinfunction "A8_27") (pintype "input"))
      (node (ref "IC15") (pin "25") (pinfunction "A8_25") (pintype "input"))
      (node (ref "IC8") (pin "27") (pinfunction "A8_27") (pintype "input"))
      (node (ref "IC9") (pin "27") (pinfunction "A8_27") (pintype "input"))
      (node (ref "X1") (pin "A10") (pinfunction "B_A10") (pintype "passive"))
    )
    (net (code "14") (name "A10") (class "Default")
      (node (ref "IC1") (pin "41") (pinfunction "A10_41") (pintype "output"))
      (node (ref "IC10") (pin "26") (pinfunction "A9_26") (pintype "input"))
      (node (ref "IC11") (pin "26") (pinfunction "A9_26") (pintype "input"))
      (node (ref "IC12") (pin "26") (pinfunction "A9_26") (pintype "input"))
      (node (ref "IC13") (pin "26") (pinfunction "A9_26") (pintype "input"))
      (node (ref "IC15") (pin "24") (pinfunction "A9_24") (pintype "input"))
      (node (ref "IC8") (pin "26") (pinfunction "A9_26") (pintype "input"))
      (node (ref "IC9") (pin "26") (pinfunction "A9_26") (pintype "input"))
      (node (ref "X1") (pin "A11") (pinfunction "B_A11") (pintype "passive"))
    )
    (net (code "15") (name "A11") (class "Default")
      (node (ref "IC1") (pin "42") (pinfunction "A11_42") (pintype "output"))
      (node (ref "IC10") (pin "23") (pinfunction "A10_23") (pintype "input"))
      (node (ref "IC11") (pin "23") (pinfunction "A10_23") (pintype "input"))
      (node (ref "IC12") (pin "23") (pinfunction "A10_23") (pintype "input"))
      (node (ref "IC13") (pin "23") (pinfunction "A10_23") (pintype "input"))
      (node (ref "IC15") (pin "21") (pinfunction "A10_21") (pintype "input"))
      (node (ref "IC8") (pin "23") (pinfunction "A10_23") (pintype "input"))
      (node (ref "IC9") (pin "23") (pinfunction "A10_23") (pintype "input"))
      (node (ref "X1") (pin "A12") (pinfunction "B_A12") (pintype "passive"))
    )
    (net (code "16") (name "A12") (class "Default")
      (node (ref "IC1") (pin "43") (pinfunction "A12_43") (pintype "output"))
      (node (ref "IC10") (pin "25") (pinfunction "A11_25") (pintype "input"))
      (node (ref "IC11") (pin "25") (pinfunction "A11_25") (pintype "input"))
      (node (ref "IC12") (pin "25") (pinfunction "A11_25") (pintype "input"))
      (node (ref "IC13") (pin "25") (pinfunction "A11_25") (pintype "input"))
      (node (ref "IC15") (pin "23") (pinfunction "A11_23") (pintype "input"))
      (node (ref "IC8") (pin "25") (pinfunction "A11_25") (pintype "input"))
      (node (ref "IC9") (pin "25") (pinfunction "A11_25") (pintype "input"))
      (node (ref "X1") (pin "A13") (pinfunction "B_A13") (pintype "passive"))
    )
    (net (code "17") (name "A13") (class "Default")
      (node (ref "IC1") (pin "44") (pinfunction "A13_44") (pintype "output"))
      (node (ref "IC10") (pin "4") (pinfunction "A12_4") (pintype "input"))
      (node (ref "IC11") (pin "4") (pinfunction "A12_4") (pintype "input"))
      (node (ref "IC12") (pin "4") (pinfunction "A12_4") (pintype "input"))
      (node (ref "IC13") (pin "4") (pinfunction "A12_4") (pintype "input"))
      (node (ref "IC15") (pin "2") (pinfunction "A12_2") (pintype "input"))
      (node (ref "IC8") (pin "4") (pinfunction "A12_4") (pintype "input"))
      (node (ref "IC9") (pin "4") (pinfunction "A12_4") (pintype "input"))
      (node (ref "X1") (pin "A14") (pinfunction "B_A14") (pintype "passive"))
    )
    (net (code "18") (name "A14") (class "Default")
      (node (ref "IC1") (pin "45") (pinfunction "A14_45") (pintype "output"))
      (node (ref "IC10") (pin "28") (pinfunction "A13_28") (pintype "input"))
      (node (ref "IC11") (pin "28") (pinfunction "A13_28") (pintype "input"))
      (node (ref "IC12") (pin "28") (pinfunction "A13_28") (pintype "input"))
      (node (ref "IC13") (pin "28") (pinfunction "A13_28") (pintype "input"))
      (node (ref "IC15") (pin "26") (pinfunction "A13_26") (pintype "input"))
      (node (ref "IC8") (pin "28") (pinfunction "A13_28") (pintype "input"))
      (node (ref "IC9") (pin "28") (pinfunction "A13_28") (pintype "input"))
      (node (ref "X1") (pin "A15") (pinfunction "B_A15") (pintype "passive"))
    )
    (net (code "19") (name "A15") (class "Default")
      (node (ref "IC1") (pin "46") (pinfunction "A15_46") (pintype "output"))
      (node (ref "IC10") (pin "3") (pinfunction "A14_3") (pintype "input"))
      (node (ref "IC11") (pin "3") (pinfunction "A14_3") (pintype "input"))
      (node (ref "IC12") (pin "29") (pinfunction "A14_29") (pintype "input"))
      (node (ref "IC13") (pin "29") (pinfunction "A14_29") (pintype "input"))
      (node (ref "IC15") (pin "1") (pinfunction "A14_1") (pintype "input"))
      (node (ref "IC8") (pin "3") (pinfunction "A14_3") (pintype "input"))
      (node (ref "IC9") (pin "3") (pinfunction "A14_3") (pintype "input"))
      (node (ref "X1") (pin "A16") (pinfunction "B_A16") (pintype "passive"))
    )
    (net (code "20") (name "A16") (class "Default")
      (node (ref "IC1") (pin "47") (pinfunction "A16_47") (pintype "output"))
      (node (ref "IC10") (pin "31") (pinfunction "A15_31") (pintype "input"))
      (node (ref "IC11") (pin "31") (pinfunction "A15_31") (pintype "input"))
      (node (ref "IC12") (pin "3") (pinfunction "A15_3") (pintype "input"))
      (node (ref "IC13") (pin "3") (pinfunction "A15_3") (pintype "input"))
      (node (ref "IC4") (pin "4") (pinfunction "I3_4") (pintype "input"))
      (node (ref "IC8") (pin "31") (pinfunction "A15_31") (pintype "input"))
      (node (ref "IC9") (pin "31") (pinfunction "A15_31") (pintype "input"))
      (node (ref "X1") (pin "A17") (pinfunction "B_A17") (pintype "passive"))
    )
    (net (code "21") (name "A17") (class "Default")
      (node (ref "IC1") (pin "48") (pinfunction "A17_48") (pintype "output"))
      (node (ref "IC10") (pin "2") (pinfunction "A16_2") (pintype "input"))
      (node (ref "IC11") (pin "2") (pinfunction "A16_2") (pintype "input"))
      (node (ref "IC12") (pin "2") (pinfunction "A16_2") (pintype "input"))
      (node (ref "IC13") (pin "2") (pinfunction "A16_2") (pintype "input"))
      (node (ref "IC4") (pin "5") (pinfunction "I4_5") (pintype "input"))
      (node (ref "IC8") (pin "2") (pinfunction "A16_2") (pintype "input"))
      (node (ref "IC9") (pin "2") (pinfunction "A16_2") (pintype "input"))
      (node (ref "X1") (pin "A18") (pinfunction "B_A18") (pintype "passive"))
    )
    (net (code "22") (name "A18") (class "Default")
      (node (ref "IC1") (pin "49") (pinfunction "A18_49") (pintype "output"))
      (node (ref "IC12") (pin "30") (pinfunction "A17_30") (pintype "input"))
      (node (ref "IC13") (pin "30") (pinfunction "A17_30") (pintype "input"))
      (node (ref "IC2") (pin "11") (pinfunction "I_11") (pintype "input"))
      (node (ref "IC4") (pin "6") (pinfunction "I5_6") (pintype "input"))
      (node (ref "X1") (pin "A19") (pinfunction "B_A19") (pintype "passive"))
    )
    (net (code "23") (name "A19") (class "Default")
      (node (ref "IC1") (pin "50") (pinfunction "A19_50") (pintype "output"))
      (node (ref "IC12") (pin "1") (pinfunction "A18_1") (pintype "input"))
      (node (ref "IC13") (pin "1") (pinfunction "A18_1") (pintype "input"))
      (node (ref "IC17") (pin "5") (pinfunction "I1_5") (pintype "input"))
      (node (ref "IC2") (pin "5") (pinfunction "I_5") (pintype "input"))
      (node (ref "IC4") (pin "11") (pinfunction "I6_11") (pintype "input"))
      (node (ref "X1") (pin "A20") (pinfunction "B_A20") (pintype "passive"))
    )
    (net (code "24") (name "A20") (class "Default")
      (node (ref "IC1") (pin "51") (pinfunction "A20_51") (pintype "output"))
      (node (ref "IC3") (pin "23") (pinfunction "A_23") (pintype "input"))
      (node (ref "X1") (pin "A21") (pinfunction "B_A21") (pintype "passive"))
    )
    (net (code "25") (name "A21") (class "Default")
      (node (ref "IC1") (pin "53") (pinfunction "A21_53") (pintype "output"))
      (node (ref "IC3") (pin "22") (pinfunction "B_22") (pintype "input"))
      (node (ref "X1") (pin "A22") (pinfunction "B_A22") (pintype "passive"))
    )
    (net (code "26") (name "A22") (class "Default")
      (node (ref "IC1") (pin "54") (pinfunction "A22_54") (pintype "output"))
      (node (ref "IC3") (pin "21") (pinfunction "C_21") (pintype "input"))
      (node (ref "X1") (pin "A23") (pinfunction "B_A23") (pintype "passive"))
    )
    (net (code "27") (name "A23") (class "Default")
      (node (ref "IC1") (pin "55") (pinfunction "A23_55") (pintype "output"))
      (node (ref "IC3") (pin "20") (pinfunction "D_20") (pintype "input"))
      (node (ref "X1") (pin "A24") (pinfunction "B_A24") (pintype "passive"))
    )
    (net (code "28") (name "CLK") (class "Default")
      (node (ref "IC1") (pin "15") (pinfunction "CLK_15") (pintype "input"))
      (node (ref "QG1") (pin "5") (pinfunction "OUT_5") (pintype "output"))
      (node (ref "X1") (pin "B26") (pinfunction "B_B26") (pintype "passive"))
    )
    (net (code "29") (name "D0") (class "Default")
      (node (ref "IC1") (pin "5") (pinfunction "D0_5") (pintype "bidirectional"))
      (node (ref "IC10") (pin "13") (pinfunction "D0_13") (pintype "bidirectional"))
      (node (ref "IC11") (pin "13") (pinfunction "D0_13") (pintype "bidirectional"))
      (node (ref "IC13") (pin "13") (pinfunction "DQ0_13") (pintype "bidirectional"))
      (node (ref "IC14") (pin "28") (pinfunction "D0_28") (pintype "bidirectional"))
      (node (ref "IC15") (pin "11") (pinfunction "DQ0_11") (pintype "bidirectional"))
      (node (ref "X1") (pin "C1") (pinfunction "B_C1") (pintype "passive"))
    )
    (net (code "30") (name "D1") (class "Default")
      (node (ref "IC1") (pin "4") (pinfunction "D1_4") (pintype "bidirectional"))
      (node (ref "IC10") (pin "14") (pinfunction "D1_14") (pintype "bidirectional"))
      (node (ref "IC11") (pin "14") (pinfunction "D1_14") (pintype "bidirectional"))
      (node (ref "IC13") (pin "14") (pinfunction "DQ1_14") (pintype "bidirectional"))
      (node (ref "IC14") (pin "18") (pinfunction "D1_18") (pintype "bidirectional"))
      (node (ref "IC15") (pin "12") (pinfunction "DQ1_12") (pintype "bidirectional"))
      (node (ref "X1") (pin "C2") (pinfunction "B_C2") (pintype "passive"))
    )
    (net (code "31") (name "D2") (class "Default")
      (node (ref "IC1") (pin "3") (pinfunction "D2_3") (pintype "bidirectional"))
      (node (ref "IC10") (pin "15") (pinfunction "D2_15") (pintype "bidirectional"))
      (node (ref "IC11") (pin "15") (pinfunction "D2_15") (pintype "bidirectional"))
      (node (ref "IC13") (pin "15") (pinfunction "DQ2_15") (pintype "bidirectional"))
      (node (ref "IC14") (pin "27") (pinfunction "D2_27") (pintype "bidirectional"))
      (node (ref "IC15") (pin "13") (pinfunction "DQ2_13") (pintype "bidirectional"))
      (node (ref "X1") (pin "C3") (pinfunction "B_C3") (pintype "passive"))
    )
    (net (code "32") (name "D3") (class "Default")
      (node (ref "IC1") (pin "2") (pinfunction "D3_2") (pintype "bidirectional"))
      (node (ref "IC10") (pin "17") (pinfunction "D3_17") (pintype "bidirectional"))
      (node (ref "IC11") (pin "17") (pinfunction "D3_17") (pintype "bidirectional"))
      (node (ref "IC13") (pin "17") (pinfunction "DQ3_17") (pintype "bidirectional"))
      (node (ref "IC14") (pin "19") (pinfunction "D3_19") (pintype "bidirectional"))
      (node (ref "IC15") (pin "15") (pinfunction "DQ3_15") (pintype "bidirectional"))
      (node (ref "X1") (pin "C4") (pinfunction "B_C4") (pintype "passive"))
    )
    (net (code "33") (name "D4") (class "Default")
      (node (ref "IC1") (pin "1") (pinfunction "D4_1") (pintype "bidirectional"))
      (node (ref "IC10") (pin "18") (pinfunction "D4_18") (pintype "bidirectional"))
      (node (ref "IC11") (pin "18") (pinfunction "D4_18") (pintype "bidirectional"))
      (node (ref "IC13") (pin "18") (pinfunction "DQ4_18") (pintype "bidirectional"))
      (node (ref "IC14") (pin "26") (pinfunction "D4_26") (pintype "bidirectional"))
      (node (ref "IC15") (pin "16") (pinfunction "DQ4_16") (pintype "bidirectional"))
      (node (ref "X1") (pin "C5") (pinfunction "B_C5") (pintype "passive"))
    )
    (net (code "34") (name "D5") (class "Default")
      (node (ref "IC1") (pin "68") (pinfunction "D5_68") (pintype "bidirectional"))
      (node (ref "IC10") (pin "19") (pinfunction "D5_19") (pintype "bidirectional"))
      (node (ref "IC11") (pin "19") (pinfunction "D5_19") (pintype "bidirectional"))
      (node (ref "IC13") (pin "19") (pinfunction "DQ5_19") (pintype "bidirectional"))
      (node (ref "IC14") (pin "20") (pinfunction "D5_20") (pintype "bidirectional"))
      (node (ref "IC15") (pin "17") (pinfunction "DQ5_17") (pintype "bidirectional"))
      (node (ref "X1") (pin "C6") (pinfunction "B_C6") (pintype "passive"))
    )
    (net (code "35") (name "D6") (class "Default")
      (node (ref "IC1") (pin "67") (pinfunction "D6_67") (pintype "bidirectional"))
      (node (ref "IC10") (pin "20") (pinfunction "D6_20") (pintype "bidirectional"))
      (node (ref "IC11") (pin "20") (pinfunction "D6_20") (pintype "bidirectional"))
      (node (ref "IC13") (pin "20") (pinfunction "DQ6_20") (pintype "bidirectional"))
      (node (ref "IC14") (pin "25") (pinfunction "D6_25") (pintype "bidirectional"))
      (node (ref "IC15") (pin "18") (pinfunction "DQ6_18") (pintype "bidirectional"))
      (node (ref "X1") (pin "C7") (pinfunction "B_C7") (pintype "passive"))
    )
    (net (code "36") (name "D7") (class "Default")
      (node (ref "IC1") (pin "66") (pinfunction "D7_66") (pintype "bidirectional"))
      (node (ref "IC10") (pin "21") (pinfunction "D7_21") (pintype "bidirectional"))
      (node (ref "IC11") (pin "21") (pinfunction "D7_21") (pintype "bidirectional"))
      (node (ref "IC13") (pin "21") (pinfunction "DQ7_21") (pintype "bidirectional"))
      (node (ref "IC14") (pin "21") (pinfunction "D7_21") (pintype "bidirectional"))
      (node (ref "IC15") (pin "19") (pinfunction "DQ7_19") (pintype "bidirectional"))
      (node (ref "X1") (pin "C8") (pinfunction "B_C8") (pintype "passive"))
    )
    (net (code "37") (name "D8") (class "Default")
      (node (ref "IC1") (pin "65") (pinfunction "D8_65") (pintype "bidirectional"))
      (node (ref "IC12") (pin "13") (pinfunction "DQ0_13") (pintype "bidirectional"))
      (node (ref "IC8") (pin "13") (pinfunction "D0_13") (pintype "bidirectional"))
      (node (ref "IC9") (pin "13") (pinfunction "D0_13") (pintype "bidirectional"))
      (node (ref "X1") (pin "C9") (pinfunction "B_C9") (pintype "passive"))
    )
    (net (code "38") (name "D9") (class "Default")
      (node (ref "IC1") (pin "64") (pinfunction "D9_64") (pintype "bidirectional"))
      (node (ref "IC12") (pin "14") (pinfunction "DQ1_14") (pintype "bidirectional"))
      (node (ref "IC8") (pin "14") (pinfunction "D1_14") (pintype "bidirectional"))
      (node (ref "IC9") (pin "14") (pinfunction "D1_14") (pintype "bidirectional"))
      (node (ref "X1") (pin "C10") (pinfunction "B_C10") (pintype "passive"))
    )
    (net (code "39") (name "D10") (class "Default")
      (node (ref "IC1") (pin "63") (pinfunction "D10_63") (pintype "bidirectional"))
      (node (ref "IC12") (pin "15") (pinfunction "DQ2_15") (pintype "bidirectional"))
      (node (ref "IC8") (pin "15") (pinfunction "D2_15") (pintype "bidirectional"))
      (node (ref "IC9") (pin "15") (pinfunction "D2_15") (pintype "bidirectional"))
      (node (ref "X1") (pin "C11") (pinfunction "B_C11") (pintype "passive"))
    )
    (net (code "40") (name "D11") (class "Default")
      (node (ref "IC1") (pin "62") (pinfunction "D11_62") (pintype "bidirectional"))
      (node (ref "IC12") (pin "17") (pinfunction "DQ3_17") (pintype "bidirectional"))
      (node (ref "IC8") (pin "17") (pinfunction "D3_17") (pintype "bidirectional"))
      (node (ref "IC9") (pin "17") (pinfunction "D3_17") (pintype "bidirectional"))
      (node (ref "X1") (pin "C12") (pinfunction "B_C12") (pintype "passive"))
    )
    (net (code "41") (name "D12") (class "Default")
      (node (ref "IC1") (pin "61") (pinfunction "D12_61") (pintype "bidirectional"))
      (node (ref "IC12") (pin "18") (pinfunction "DQ4_18") (pintype "bidirectional"))
      (node (ref "IC8") (pin "18") (pinfunction "D4_18") (pintype "bidirectional"))
      (node (ref "IC9") (pin "18") (pinfunction "D4_18") (pintype "bidirectional"))
      (node (ref "X1") (pin "C13") (pinfunction "B_C13") (pintype "passive"))
    )
    (net (code "42") (name "D13") (class "Default")
      (node (ref "IC1") (pin "60") (pinfunction "D13_60") (pintype "bidirectional"))
      (node (ref "IC12") (pin "19") (pinfunction "DQ5_19") (pintype "bidirectional"))
      (node (ref "IC8") (pin "19") (pinfunction "D5_19") (pintype "bidirectional"))
      (node (ref "IC9") (pin "19") (pinfunction "D5_19") (pintype "bidirectional"))
      (node (ref "X1") (pin "C14") (pinfunction "B_C14") (pintype "passive"))
    )
    (net (code "43") (name "D14") (class "Default")
      (node (ref "IC1") (pin "59") (pinfunction "D14_59") (pintype "bidirectional"))
      (node (ref "IC12") (pin "20") (pinfunction "DQ6_20") (pintype "bidirectional"))
      (node (ref "IC8") (pin "20") (pinfunction "D6_20") (pintype "bidirectional"))
      (node (ref "IC9") (pin "20") (pinfunction "D6_20") (pintype "bidirectional"))
      (node (ref "X1") (pin "C15") (pinfunction "B_C15") (pintype "passive"))
    )
    (net (code "44") (name "D15") (class "Default")
      (node (ref "IC1") (pin "58") (pinfunction "D15_58") (pintype "bidirectional"))
      (node (ref "IC12") (pin "21") (pinfunction "DQ7_21") (pintype "bidirectional"))
      (node (ref "IC8") (pin "21") (pinfunction "D7_21") (pintype "bidirectional"))
      (node (ref "IC9") (pin "21") (pinfunction "D7_21") (pintype "bidirectional"))
      (node (ref "X1") (pin "C16") (pinfunction "B_C16") (pintype "passive"))
    )
    (net (code "45") (name "DTACK") (class "Default")
      (node (ref "IC2") (pin "9") (pinfunction "I_9") (pintype "input"))
      (node (ref "IC6") (pin "8") (pinfunction "O_8") (pintype "output"))
    )
    (net (code "46") (name "FC0") (class "Default")
      (node (ref "IC1") (pin "30") (pinfunction "FC0_30") (pintype "output"))
      (node (ref "IC4") (pin "1") (pinfunction "I0_1") (pintype "input"))
      (node (ref "X1") (pin "B6") (pinfunction "B_B6") (pintype "passive"))
    )
    (net (code "47") (name "FC1") (class "Default")
      (node (ref "IC1") (pin "29") (pinfunction "FC1_29") (pintype "output"))
      (node (ref "IC4") (pin "2") (pinfunction "I1_2") (pintype "input"))
      (node (ref "X1") (pin "B7") (pinfunction "B_B7") (pintype "passive"))
    )
    (net (code "48") (name "FC2") (class "Default")
      (node (ref "IC1") (pin "28") (pinfunction "FC2_28") (pintype "output"))
      (node (ref "IC4") (pin "3") (pinfunction "I2_3") (pintype "input"))
      (node (ref "X1") (pin "B8") (pinfunction "B_B8") (pintype "passive"))
    )
    (net (code "49") (name "GND") (class "Default")
      (node (ref "C1") (pin "2") (pinfunction "2_2") (pintype "passive"))
      (node (ref "C10") (pin "2") (pinfunction "2_2") (pintype "passive"))
      (node (ref "C11") (pin "-") (pinfunction "-_-") (pintype "passive"))
      (node (ref "C12") (pin "2") (pinfunction "2_2") (pintype "passive"))
      (node (ref "C13") (pin "2") (pinfunction "2_2") (pintype "passive"))
      (node (ref "C14") (pin "2") (pinfunction "2_2") (pintype "passive"))
      (node (ref "C15") (pin "2") (pinfunction "2_2") (pintype "passive"))
      (node (ref "C16") (pin "2") (pinfunction "2_2") (pintype "passive"))
      (node (ref "C17") (pin "2") (pinfunction "2_2") (pintype "passive"))
      (node (ref "C18") (pin "2") (pinfunction "2_2") (pintype "passive"))
      (node (ref "C19") (pin "-") (pinfunction "-_-") (pintype "passive"))
      (node (ref "C2") (pin "2") (pinfunction "2_2") (pintype "passive"))
      (node (ref "C20") (pin "2") (pinfunction "2_2") (pintype "passive"))
      (node (ref "C21") (pin "2") (pinfunction "2_2") (pintype "passive"))
      (node (ref "C22") (pin "2") (pinfunction "2_2") (pintype "passive"))
      (node (ref "C23") (pin "2") (pinfunction "2_2") (pintype "passive"))
      (node (ref "C24") (pin "-") (pinfunction "-_-") (pintype "passive"))
      (node (ref "C25") (pin "2") (pinfunction "2_2") (pintype "passive"))
      (node (ref "C26") (pin "2") (pinfunction "2_2") (pintype "passive"))
      (node (ref "C27") (pin "-") (pinfunction "-_-") (pintype "passive"))
      (node (ref "C28") (pin "2") (pinfunction "2_2") (pintype "passive"))
      (node (ref "C29") (pin "2") (pinfunction "2_2") (pintype "passive"))
      (node (ref "C3") (pin "2") (pinfunction "2_2") (pintype "passive"))
      (node (ref "C30") (pin "2") (pinfunction "2_2") (pintype "passive"))
      (node (ref "C31") (pin "1") (pinfunction "1_1") (pintype "passive"))
      (node (ref "C32") (pin "-") (pinfunction "-_-") (pintype "passive"))
      (node (ref "C36") (pin "+") (pinfunction "+_+") (pintype "passive"))
      (node (ref "C37") (pin "2") (pinfunction "2_2") (pintype "passive"))
      (node (ref "C38") (pin "2") (pinfunction "2_2") (pintype "passive"))
      (node (ref "C39") (pin "2") (pinfunction "2_2") (pintype "passive"))
      (node (ref "C4") (pin "-") (pinfunction "-_-") (pintype "passive"))
      (node (ref "C40") (pin "-") (pinfunction "-_-") (pintype "passive"))
      (node (ref "C5") (pin "2") (pinfunction "2_2") (pintype "passive"))
      (node (ref "C6") (pin "2") (pinfunction "2_2") (pintype "passive"))
      (node (ref "C7") (pin "2") (pinfunction "2_2") (pintype "passive"))
      (node (ref "C8") (pin "-") (pinfunction "-_-") (pintype "passive"))
      (node (ref "C9") (pin "2") (pinfunction "2_2") (pintype "passive"))
      (node (ref "IC1") (pin "16") (pinfunction "GND_16") (pintype "power_in"))
      (node (ref "IC1") (pin "17") (pinfunction "GND_17") (pintype "power_in"))
      (node (ref "IC1") (pin "56") (pinfunction "GND_56") (pintype "power_in"))
      (node (ref "IC1") (pin "57") (pinfunction "GND_57") (pintype "power_in"))
      (node (ref "IC10") (pin "16") (pinfunction "GND_16") (pintype "power_in"))
      (node (ref "IC11") (pin "16") (pinfunction "GND_16") (pintype "power_in"))
      (node (ref "IC12") (pin "16") (pinfunction "GND_16") (pintype "power_in"))
      (node (ref "IC13") (pin "16") (pinfunction "GND_16") (pintype "power_in"))
      (node (ref "IC14") (pin "22") (pinfunction "GND_22") (pintype "power_in"))
      (node (ref "IC15") (pin "14") (pinfunction "GND_14") (pintype "power_in"))
      (node (ref "IC16") (pin "15") (pinfunction "GND_15") (pintype "power_in"))
      (node (ref "IC17") (pin "7") (pinfunction "GND_7") (pintype "power_in"))
      (node (ref "IC2") (pin "7") (pinfunction "GND_7") (pintype "power_in"))
      (node (ref "IC3") (pin "12") (pinfunction "GND_12") (pintype "power_in"))
      (node (ref "IC4") (pin "7") (pinfunction "GND_7") (pintype "power_in"))
      (node (ref "IC5") (pin "10") (pinfunction "0_10") (pintype "input"))
      (node (ref "IC5") (pin "5") (pinfunction "EI_5") (pintype "input"))
      (node (ref "IC5") (pin "8") (pinfunction "GND_8") (pintype "power_in"))
      (node (ref "IC6") (pin "7") (pinfunction "GND_7") (pintype "power_in"))
      (node (ref "IC7") (pin "7") (pinfunction "GND_7") (pintype "power_in"))
      (node (ref "IC8") (pin "16") (pinfunction "GND_16") (pintype "power_in"))
      (node (ref "IC9") (pin "16") (pinfunction "GND_16") (pintype "power_in"))
      (node (ref "LED1") (pin "C") (pinfunction "C_C") (pintype "passive"))
      (node (ref "LED10") (pin "C") (pinfunction "C_C") (pintype "passive"))
      (node (ref "LED4") (pin "C") (pinfunction "C_C") (pintype "passive"))
      (node (ref "LED5") (pin "C") (pinfunction "C_C") (pintype "passive"))
      (node (ref "LED6") (pin "C") (pinfunction "C_C") (pintype "passive"))
      (node (ref "LED7") (pin "C") (pinfunction "C_C") (pintype "passive"))
      (node (ref "LED8") (pin "C") (pinfunction "C_C") (pintype "passive"))
      (node (ref "LED9") (pin "C") (pinfunction "C_C") (pintype "passive"))
      (node (ref "QG1") (pin "4") (pinfunction "GND_4") (pintype "power_in"))
      (node (ref "R12") (pin "2") (pinfunction "2_2") (pintype "passive"))
      (node (ref "R13") (pin "2") (pinfunction "2_2") (pintype "passive"))
      (node (ref "X1") (pin "A25") (pinfunction "B_A25") (pintype "passive"))
      (node (ref "X1") (pin "A26") (pinfunction "B_A26") (pintype "passive"))
      (node (ref "X1") (pin "A27") (pinfunction "B_A27") (pintype "passive"))
      (node (ref "X1") (pin "A28") (pinfunction "B_A28") (pintype "passive"))
      (node (ref "X1") (pin "A29") (pinfunction "B_A29") (pintype "passive"))
      (node (ref "X1") (pin "A30") (pinfunction "B_A30") (pintype "passive"))
      (node (ref "X1") (pin "A31") (pinfunction "B_A31") (pintype "passive"))
      (node (ref "X1") (pin "A32") (pinfunction "B_A32") (pintype "passive"))
      (node (ref "X1") (pin "B25") (pinfunction "B_B25") (pintype "passive"))
      (node (ref "X1") (pin "B27") (pinfunction "B_B27") (pintype "passive"))
      (node (ref "X1") (pin "B30") (pinfunction "B_B30") (pintype "passive"))
      (node (ref "X1") (pin "B31") (pinfunction "B_B31") (pintype "passive"))
      (node (ref "X1") (pin "B32") (pinfunction "B_B32") (pintype "passive"))
      (node (ref "X2") (pin "5") (pinfunction "5_5") (pintype "passive"))
      (node (ref "X2") (pin "G1") (pinfunction "G1_G1") (pintype "passive"))
      (node (ref "X2") (pin "G2") (pinfunction "G2_G2") (pintype "passive"))
      (node (ref "X3") (pin "5") (pinfunction "5_5") (pintype "passive"))
      (node (ref "X3") (pin "G1") (pinfunction "G1_G1") (pintype "passive"))
      (node (ref "X3") (pin "G2") (pinfunction "G2_G2") (pintype "passive"))
    )
    (net (code "50") (name "GPIO_OUT0") (class "Default")
      (node (ref "IC14") (pin "32") (pinfunction "OP0_32") (pintype "output"))
      (node (ref "R14") (pin "1") (pinfunction "1_1") (pintype "passive"))
    )
    (net (code "51") (name "GPIO_OUT1") (class "Default")
      (node (ref "IC14") (pin "14") (pinfunction "OP1_14") (pintype "output"))
      (node (ref "R15") (pin "1") (pinfunction "1_1") (pintype "passive"))
    )
    (net (code "52") (name "GPIO_OUT2") (class "Default")
      (node (ref "IC14") (pin "15") (pinfunction "OP3_15") (pintype "output"))
      (node (ref "R16") (pin "1") (pinfunction "1_1") (pintype "passive"))
    )
    (net (code "53") (name "GPIO_OUT3") (class "Default")
      (node (ref "IC14") (pin "30") (pinfunction "OP4_30") (pintype "output"))
      (node (ref "R17") (pin "1") (pinfunction "1_1") (pintype "passive"))
    )
    (net (code "54") (name "GPIO_OUT4") (class "Default")
      (node (ref "IC14") (pin "16") (pinfunction "OP5_16") (pintype "output"))
      (node (ref "R18") (pin "1") (pinfunction "1_1") (pintype "passive"))
    )
    (net (code "55") (name "GPIO_OUT5") (class "Default")
      (node (ref "IC14") (pin "29") (pinfunction "OP6_29") (pintype "output"))
      (node (ref "R19") (pin "1") (pinfunction "1_1") (pintype "passive"))
    )
    (net (code "56") (name "GPIO_OUT6") (class "Default")
      (node (ref "IC14") (pin "17") (pinfunction "OP7_17") (pintype "output"))
      (node (ref "R20") (pin "1") (pinfunction "1_1") (pintype "passive"))
    )
    (net (code "57") (name "NMI_SW") (class "Default")
      (node (ref "C12") (pin "1") (pinfunction "1_1") (pintype "passive"))
      (node (ref "IC7") (pin "13") (pinfunction "I_13") (pintype "input"))
      (node (ref "R10") (pin "1") (pinfunction "1_1") (pintype "passive"))
      (node (ref "R12") (pin "1") (pinfunction "1_1") (pintype "passive"))
    )
    (net (code "58") (name "Net-(IC16A-C1+)") (class "Default")
      (node (ref "C33") (pin "+") (pinfunction "+_+") (pintype "passive"))
      (node (ref "IC16") (pin "1") (pinfunction "C1+_1") (pintype "bidirectional"))
    )
    (net (code "59") (name "Net-(IC16A-C1-)") (class "Default")
      (node (ref "C33") (pin "-") (pinfunction "-_-") (pintype "passive"))
      (node (ref "IC16") (pin "3") (pinfunction "C1-_3") (pintype "bidirectional"))
    )
    (net (code "60") (name "Net-(IC16A-C2+)") (class "Default")
      (node (ref "C34") (pin "+") (pinfunction "+_+") (pintype "passive"))
      (node (ref "IC16") (pin "4") (pinfunction "C2+_4") (pintype "bidirectional"))
    )
    (net (code "61") (name "Net-(IC16A-C2-)") (class "Default")
      (node (ref "C34") (pin "-") (pinfunction "-_-") (pintype "passive"))
      (node (ref "IC16") (pin "5") (pinfunction "C2-_5") (pintype "bidirectional"))
    )
    (net (code "62") (name "Net-(IC16A-V+)") (class "Default")
      (node (ref "C35") (pin "+") (pinfunction "+_+") (pintype "passive"))
      (node (ref "IC16") (pin "2") (pinfunction "V+_2") (pintype "bidirectional"))
    )
    (net (code "63") (name "Net-(IC16A-V-)") (class "Default")
      (node (ref "C36") (pin "-") (pinfunction "-_-") (pintype "passive"))
      (node (ref "IC16") (pin "6") (pinfunction "V-_6") (pintype "bidirectional"))
    )
    (net (code "64") (name "Net-(LED1-PadA)") (class "Default")
      (node (ref "LED1") (pin "A") (pinfunction "A_A") (pintype "passive"))
      (node (ref "R3") (pin "2") (pinfunction "2_2") (pintype "passive"))
    )
    (net (code "65") (name "Net-(LED2-PadA)") (class "Default")
      (node (ref "LED2") (pin "A") (pinfunction "A_A") (pintype "passive"))
      (node (ref "R1") (pin "2") (pinfunction "2_2") (pintype "passive"))
    )
    (net (code "66") (name "Net-(LED3-PadA)") (class "Default")
      (node (ref "LED3") (pin "A") (pinfunction "A_A") (pintype "passive"))
      (node (ref "R2") (pin "2") (pinfunction "2_2") (pintype "passive"))
    )
    (net (code "67") (name "Net-(LED4-PadA)") (class "Default")
      (node (ref "LED4") (pin "A") (pinfunction "A_A") (pintype "passive"))
      (node (ref "R14") (pin "2") (pinfunction "2_2") (pintype "passive"))
    )
    (net (code "68") (name "Net-(LED5-PadA)") (class "Default")
      (node (ref "LED5") (pin "A") (pinfunction "A_A") (pintype "passive"))
      (node (ref "R15") (pin "2") (pinfunction "2_2") (pintype "passive"))
    )
    (net (code "69") (name "Net-(LED6-PadA)") (class "Default")
      (node (ref "LED6") (pin "A") (pinfunction "A_A") (pintype "passive"))
      (node (ref "R16") (pin "2") (pinfunction "2_2") (pintype "passive"))
    )
    (net (code "70") (name "Net-(LED7-PadA)") (class "Default")
      (node (ref "LED7") (pin "A") (pinfunction "A_A") (pintype "passive"))
      (node (ref "R17") (pin "2") (pinfunction "2_2") (pintype "passive"))
    )
    (net (code "71") (name "Net-(LED8-PadA)") (class "Default")
      (node (ref "LED8") (pin "A") (pinfunction "A_A") (pintype "passive"))
      (node (ref "R18") (pin "2") (pinfunction "2_2") (pintype "passive"))
    )
    (net (code "72") (name "Net-(LED9-PadA)") (class "Default")
      (node (ref "LED9") (pin "A") (pinfunction "A_A") (pintype "passive"))
      (node (ref "R19") (pin "2") (pinfunction "2_2") (pintype "passive"))
    )
    (net (code "73") (name "Net-(LED10-PadA)") (class "Default")
      (node (ref "LED10") (pin "A") (pinfunction "A_A") (pintype "passive"))
      (node (ref "R20") (pin "2") (pinfunction "2_2") (pintype "passive"))
    )
    (net (code "74") (name "Net-(S1-S)") (class "Default")
      (node (ref "R10") (pin "2") (pinfunction "2_2") (pintype "passive"))
      (node (ref "S1") (pin "1") (pinfunction "S_1") (pintype "passive"))
      (node (ref "S1") (pin "2") (pinfunction "S1_2") (pintype "passive"))
    )
    (net (code "75") (name "Net-(S2-S)") (class "Default")
      (node (ref "R11") (pin "2") (pinfunction "2_2") (pintype "passive"))
      (node (ref "S2") (pin "1") (pinfunction "S_1") (pintype "passive"))
      (node (ref "S2") (pin "2") (pinfunction "S1_2") (pintype "passive"))
    )
    (net (code "76") (name "REGION15") (class "Default")
      (node (ref "IC17") (pin "1") (pinfunction "I0_1") (pintype "input"))
      (node (ref "IC17") (pin "4") (pinfunction "I0_4") (pintype "input"))
      (node (ref "IC2") (pin "4") (pinfunction "O_4") (pintype "output"))
    )
    (net (code "77") (name "RESET_SW") (class "Default")
      (node (ref "C13") (pin "1") (pinfunction "1_1") (pintype "passive"))
      (node (ref "IC7") (pin "11") (pinfunction "I_11") (pintype "input"))
      (node (ref "IC7") (pin "9") (pinfunction "I_9") (pintype "input"))
      (node (ref "R11") (pin "1") (pinfunction "1_1") (pintype "passive"))
      (node (ref "R13") (pin "1") (pinfunction "1_1") (pintype "passive"))
    )
    (net (code "78") (name "RS232_0_RX") (class "Default")
      (node (ref "IC16") (pin "14") (pinfunction "T1OUT_14") (pintype "output"))
      (node (ref "X2") (pin "2") (pinfunction "2_2") (pintype "passive"))
    )
    (net (code "79") (name "RS232_0_TX") (class "Default")
      (node (ref "IC16") (pin "13") (pinfunction "R1IN_13") (pintype "input"))
      (node (ref "X2") (pin "3") (pinfunction "3_3") (pintype "passive"))
    )
    (net (code "80") (name "RS232_1_RX") (class "Default")
      (node (ref "IC16") (pin "7") (pinfunction "T2OUT_7") (pintype "output"))
      (node (ref "X3") (pin "2") (pinfunction "2_2") (pintype "passive"))
    )
    (net (code "81") (name "RS232_1_TX") (class "Default")
      (node (ref "IC16") (pin "8") (pinfunction "R2IN_8") (pintype "input"))
      (node (ref "X3") (pin "3") (pinfunction "3_3") (pintype "passive"))
    )
    (net (code "82") (name "R{slash}~{W}") (class "Default")
      (node (ref "IC10") (pin "29") (pinfunction "~{WE}_29") (pintype "input"))
      (node (ref "IC11") (pin "29") (pinfunction "~{WE}_29") (pintype "input"))
      (node (ref "IC12") (pin "31") (pinfunction "~{WE}_31") (pintype "input"))
      (node (ref "IC13") (pin "31") (pinfunction "~{WE}_31") (pintype "input"))
      (node (ref "IC14") (pin "9") (pinfunction "R/~{W}_9") (pintype "input"))
      (node (ref "IC15") (pin "27") (pinfunction "~{WE}_27") (pintype "input"))
      (node (ref "IC8") (pin "29") (pinfunction "~{WE}_29") (pintype "input"))
      (node (ref "IC9") (pin "29") (pinfunction "~{WE}_29") (pintype "input"))
    )
    (net (code "83") (name "R~{W}") (class "Default")
      (node (ref "IC1") (pin "9") (pinfunction "R/W_9") (pintype "output"))
      (node (ref "IC2") (pin "1") (pinfunction "I_1") (pintype "input"))
      (node (ref "X1") (pin "B22") (pinfunction "B_B22") (pintype "passive"))
    )
    (net (code "84") (name "UART0_RX") (class "Default")
      (node (ref "IC14") (pin "35") (pinfunction "RXDA_35") (pintype "input"))
      (node (ref "IC16") (pin "12") (pinfunction "R1OUT_12") (pintype "output"))
    )
    (net (code "85") (name "UART0_TX") (class "Default")
      (node (ref "IC14") (pin "33") (pinfunction "TXDA_33") (pintype "output"))
      (node (ref "IC16") (pin "11") (pinfunction "T1IN_11") (pintype "input"))
    )
    (net (code "86") (name "UART1_RX") (class "Default")
      (node (ref "IC14") (pin "11") (pinfunction "RXDB_11") (pintype "output"))
      (node (ref "IC16") (pin "9") (pinfunction "R2OUT_9") (pintype "output"))
    )
    (net (code "87") (name "UART1_TX") (class "Default")
      (node (ref "IC14") (pin "13") (pinfunction "TXDB_13") (pintype "bidirectional"))
      (node (ref "IC16") (pin "10") (pinfunction "T2IN_10") (pintype "input"))
    )
    (net (code "88") (name "unconnected-(IC1A-E-Pad22)") (class "Default")
      (node (ref "IC1") (pin "22") (pinfunction "E_22") (pintype "output"))
    )
    (net (code "89") (name "unconnected-(IC1A-VMA-Pad21)") (class "Default")
      (node (ref "IC1") (pin "21") (pinfunction "VMA_21") (pintype "output"))
    )
    (net (code "90") (name "unconnected-(IC3A-2-Pad3)") (class "Default")
      (node (ref "IC3") (pin "3") (pinfunction "2_3") (pintype "output"))
    )
    (net (code "91") (name "unconnected-(IC3A-3-Pad4)") (class "Default")
      (node (ref "IC3") (pin "4") (pinfunction "3_4") (pintype "output"))
    )
    (net (code "92") (name "unconnected-(IC3A-4-Pad5)") (class "Default")
      (node (ref "IC3") (pin "5") (pinfunction "4_5") (pintype "output"))
    )
    (net (code "93") (name "unconnected-(IC3A-5-Pad6)") (class "Default")
      (node (ref "IC3") (pin "6") (pinfunction "5_6") (pintype "output"))
    )
    (net (code "94") (name "unconnected-(IC3A-6-Pad7)") (class "Default")
      (node (ref "IC3") (pin "7") (pinfunction "6_7") (pintype "output"))
    )
    (net (code "95") (name "unconnected-(IC3A-7-Pad8)") (class "Default")
      (node (ref "IC3") (pin "8") (pinfunction "7_8") (pintype "output"))
    )
    (net (code "96") (name "unconnected-(IC3A-8-Pad9)") (class "Default")
      (node (ref "IC3") (pin "9") (pinfunction "8_9") (pintype "output"))
    )
    (net (code "97") (name "unconnected-(IC3A-9-Pad10)") (class "Default")
      (node (ref "IC3") (pin "10") (pinfunction "9_10") (pintype "output"))
    )
    (net (code "98") (name "unconnected-(IC3A-10-Pad11)") (class "Default")
      (node (ref "IC3") (pin "11") (pinfunction "10_11") (pintype "output"))
    )
    (net (code "99") (name "unconnected-(IC3A-11-Pad13)") (class "Default")
      (node (ref "IC3") (pin "13") (pinfunction "11_13") (pintype "output"))
    )
    (net (code "100") (name "unconnected-(IC3A-12-Pad14)") (class "Default")
      (node (ref "IC3") (pin "14") (pinfunction "12_14") (pintype "output"))
    )
    (net (code "101") (name "unconnected-(IC3A-13-Pad15)") (class "Default")
      (node (ref "IC3") (pin "15") (pinfunction "13_15") (pintype "output"))
    )
    (net (code "102") (name "unconnected-(IC3A-14-Pad16)") (class "Default")
      (node (ref "IC3") (pin "16") (pinfunction "14_16") (pintype "output"))
    )
    (net (code "103") (name "unconnected-(IC5A-EO-Pad15)") (class "Default")
      (node (ref "IC5") (pin "15") (pinfunction "EO_15") (pintype "output"))
    )
    (net (code "104") (name "unconnected-(IC5A-GS-Pad14)") (class "Default")
      (node (ref "IC5") (pin "14") (pinfunction "GS_14") (pintype "output"))
    )
    (net (code "105") (name "unconnected-(IC14-IP0-Pad8)") (class "Default")
      (node (ref "IC14") (pin "8") (pinfunction "IP0_8") (pintype "input"))
    )
    (net (code "106") (name "unconnected-(IC14-IP1-Pad5)") (class "Default")
      (node (ref "IC14") (pin "5") (pinfunction "IP1_5") (pintype "input"))
    )
    (net (code "107") (name "unconnected-(IC14-IP2-Pad40)") (class "Default")
      (node (ref "IC14") (pin "40") (pinfunction "IP2_40") (pintype "input"))
    )
    (net (code "108") (name "unconnected-(IC14-IP3-Pad3)") (class "Default")
      (node (ref "IC14") (pin "3") (pinfunction "IP3_3") (pintype "input"))
    )
    (net (code "109") (name "unconnected-(IC14-IP4-Pad43)") (class "Default")
      (node (ref "IC14") (pin "43") (pinfunction "IP4_43") (pintype "input"))
    )
    (net (code "110") (name "unconnected-(IC14-IP5-Pad42)") (class "Default")
      (node (ref "IC14") (pin "42") (pinfunction "IP5_42") (pintype "input"))
    )
    (net (code "111") (name "unconnected-(IC14-OP2-Pad31)") (class "Default")
      (node (ref "IC14") (pin "31") (pinfunction "OP2_31") (pintype "output"))
    )
    (net (code "112") (name "unconnected-(IC14-~{IACK}-Pad41)") (class "Default")
      (node (ref "IC14") (pin "41") (pinfunction "~{IACK}_41") (pintype "input"))
    )
    (net (code "113") (name "unconnected-(QG1-TS-Pad1)") (class "Default")
      (node (ref "QG1") (pin "1") (pinfunction "TS_1") (pintype "passive"))
    )
    (net (code "114") (name "unconnected-(R5-Pad1)") (class "Default")
      (node (ref "R5") (pin "1") (pinfunction "1_1") (pintype "passive"))
    )
    (net (code "115") (name "unconnected-(R6-Pad1)") (class "Default")
      (node (ref "R6") (pin "1") (pinfunction "1_1") (pintype "passive"))
    )
    (net (code "116") (name "unconnected-(R7-Pad1)") (class "Default")
      (node (ref "R7") (pin "1") (pinfunction "1_1") (pintype "passive"))
    )
    (net (code "117") (name "unconnected-(X1A-B-PadA1)") (class "Default")
      (node (ref "X1") (pin "A1") (pinfunction "B_A1") (pintype "passive"))
    )
    (net (code "118") (name "unconnected-(X1AN-B-PadB16)") (class "Default")
      (node (ref "X1") (pin "B16") (pinfunction "B_B16") (pintype "passive"))
    )
    (net (code "119") (name "unconnected-(X1AP-B-PadB18)") (class "Default")
      (node (ref "X1") (pin "B18") (pinfunction "B_B18") (pintype "passive"))
    )
    (net (code "120") (name "unconnected-(X1AQ-B-PadB19)") (class "Default")
      (node (ref "X1") (pin "B19") (pinfunction "B_B19") (pintype "passive"))
    )
    (net (code "121") (name "unconnected-(X1AS-B-PadB20)") (class "Default")
      (node (ref "X1") (pin "B20") (pinfunction "B_B20") (pintype "passive"))
    )
    (net (code "122") (name "unconnected-(X1BB-B-PadB29)") (class "Default")
      (node (ref "X1") (pin "B29") (pinfunction "B_B29") (pintype "passive"))
    )
    (net (code "123") (name "unconnected-(X1BG-B-PadB4)") (class "Default")
      (node (ref "X1") (pin "B4") (pinfunction "B_B4") (pintype "passive"))
    )
    (net (code "124") (name "unconnected-(X1BH-B-PadB5)") (class "Default")
      (node (ref "X1") (pin "B5") (pinfunction "B_B5") (pintype "passive"))
    )
    (net (code "125") (name "unconnected-(X1BU-B-PadC17)") (class "Default")
      (node (ref "X1") (pin "C17") (pinfunction "B_C17") (pintype "passive"))
    )
    (net (code "126") (name "unconnected-(X1BV-B-PadC18)") (class "Default")
      (node (ref "X1") (pin "C18") (pinfunction "B_C18") (pintype "passive"))
    )
    (net (code "127") (name "unconnected-(X1BW-B-PadC19)") (class "Default")
      (node (ref "X1") (pin "C19") (pinfunction "B_C19") (pintype "passive"))
    )
    (net (code "128") (name "unconnected-(X1BY-B-PadC20)") (class "Default")
      (node (ref "X1") (pin "C20") (pinfunction "B_C20") (pintype "passive"))
    )
    (net (code "129") (name "unconnected-(X1BZ-B-PadC21)") (class "Default")
      (node (ref "X1") (pin "C21") (pinfunction "B_C21") (pintype "passive"))
    )
    (net (code "130") (name "unconnected-(X1CA-B-PadC22)") (class "Default")
      (node (ref "X1") (pin "C22") (pinfunction "B_C22") (pintype "passive"))
    )
    (net (code "131") (name "unconnected-(X1CB-B-PadC23)") (class "Default")
      (node (ref "X1") (pin "C23") (pinfunction "B_C23") (pintype "passive"))
    )
    (net (code "132") (name "unconnected-(X1CC-B-PadC24)") (class "Default")
      (node (ref "X1") (pin "C24") (pinfunction "B_C24") (pintype "passive"))
    )
    (net (code "133") (name "unconnected-(X1CD-B-PadC25)") (class "Default")
      (node (ref "X1") (pin "C25") (pinfunction "B_C25") (pintype "passive"))
    )
    (net (code "134") (name "unconnected-(X1CE-B-PadC26)") (class "Default")
      (node (ref "X1") (pin "C26") (pinfunction "B_C26") (pintype "passive"))
    )
    (net (code "135") (name "unconnected-(X1CF-B-PadC27)") (class "Default")
      (node (ref "X1") (pin "C27") (pinfunction "B_C27") (pintype "passive"))
    )
    (net (code "136") (name "unconnected-(X1CG-B-PadC28)") (class "Default")
      (node (ref "X1") (pin "C28") (pinfunction "B_C28") (pintype "passive"))
    )
    (net (code "137") (name "unconnected-(X1CH-B-PadC29)") (class "Default")
      (node (ref "X1") (pin "C29") (pinfunction "B_C29") (pintype "passive"))
    )
    (net (code "138") (name "unconnected-(X1CJ-B-PadC30)") (class "Default")
      (node (ref "X1") (pin "C30") (pinfunction "B_C30") (pintype "passive"))
    )
    (net (code "139") (name "unconnected-(X1CK-B-PadC31)") (class "Default")
      (node (ref "X1") (pin "C31") (pinfunction "B_C31") (pintype "passive"))
    )
    (net (code "140") (name "unconnected-(X1CL-B-PadC32)") (class "Default")
      (node (ref "X1") (pin "C32") (pinfunction "B_C32") (pintype "passive"))
    )
    (net (code "141") (name "unconnected-(X2-Pad1)") (class "Default")
      (node (ref "X2") (pin "1") (pinfunction "1_1") (pintype "passive"))
    )
    (net (code "142") (name "unconnected-(X2-Pad4)") (class "Default")
      (node (ref "X2") (pin "4") (pinfunction "4_4") (pintype "passive"))
    )
    (net (code "143") (name "unconnected-(X2-Pad6)") (class "Default")
      (node (ref "X2") (pin "6") (pinfunction "6_6") (pintype "passive"))
    )
    (net (code "144") (name "unconnected-(X2-Pad7)") (class "Default")
      (node (ref "X2") (pin "7") (pinfunction "7_7") (pintype "passive"))
    )
    (net (code "145") (name "unconnected-(X2-Pad8)") (class "Default")
      (node (ref "X2") (pin "8") (pinfunction "8_8") (pintype "passive"))
    )
    (net (code "146") (name "unconnected-(X2-Pad9)") (class "Default")
      (node (ref "X2") (pin "9") (pinfunction "9_9") (pintype "passive"))
    )
    (net (code "147") (name "unconnected-(X3-Pad1)") (class "Default")
      (node (ref "X3") (pin "1") (pinfunction "1_1") (pintype "passive"))
    )
    (net (code "148") (name "unconnected-(X3-Pad4)") (class "Default")
      (node (ref "X3") (pin "4") (pinfunction "4_4") (pintype "passive"))
    )
    (net (code "149") (name "unconnected-(X3-Pad6)") (class "Default")
      (node (ref "X3") (pin "6") (pinfunction "6_6") (pintype "passive"))
    )
    (net (code "150") (name "unconnected-(X3-Pad7)") (class "Default")
      (node (ref "X3") (pin "7") (pinfunction "7_7") (pintype "passive"))
    )
    (net (code "151") (name "unconnected-(X3-Pad8)") (class "Default")
      (node (ref "X3") (pin "8") (pinfunction "8_8") (pintype "passive"))
    )
    (net (code "152") (name "unconnected-(X3-Pad9)") (class "Default")
      (node (ref "X3") (pin "9") (pinfunction "9_9") (pintype "passive"))
    )
    (net (code "153") (name "{slash}AS") (class "Default")
      (node (ref "IC3") (pin "18") (pinfunction "G1_18") (pintype "input"))
      (node (ref "IC3") (pin "19") (pinfunction "G2_19") (pintype "input"))
    )
    (net (code "154") (name "~{68681_CS}") (class "Default")
      (node (ref "IC14") (pin "39") (pinfunction "~{CS}_39") (pintype "input"))
      (node (ref "IC17") (pin "3") (pinfunction "O_3") (pintype "output"))
    )
    (net (code "155") (name "~{68681_DTACK}") (class "Default")
      (node (ref "IC14") (pin "10") (pinfunction "~{DTACK}_10") (pintype "output"))
      (node (ref "IC6") (pin "2") (pinfunction "I1_2") (pintype "input"))
      (node (ref "R9") (pin "2") (pinfunction "2_2") (pintype "passive"))
    )
    (net (code "156") (name "~{68681_IRQ}") (class "Default")
      (node (ref "IC14") (pin "24") (pinfunction "~{INTR}_24") (pintype "output"))
      (node (ref "IC5") (pin "2") (pinfunction "5_2") (pintype "input"))
      (node (ref "R5") (pin "2") (pinfunction "2_2") (pintype "passive"))
    )
    (net (code "157") (name "~{A18}") (class "Default")
      (node (ref "IC10") (pin "30") (pinfunction "CE2_30") (pintype "input"))
      (node (ref "IC11") (pin "30") (pinfunction "CE2_30") (pintype "input"))
      (node (ref "IC2") (pin "10") (pinfunction "O_10") (pintype "output"))
      (node (ref "IC8") (pin "30") (pinfunction "CE2_30") (pintype "input"))
      (node (ref "IC9") (pin "30") (pinfunction "CE2_30") (pintype "input"))
    )
    (net (code "158") (name "~{A19}") (class "Default")
      (node (ref "IC17") (pin "2") (pinfunction "I1_2") (pintype "input"))
      (node (ref "IC2") (pin "6") (pinfunction "O_6") (pintype "output"))
    )
    (net (code "159") (name "~{AS}") (class "Default")
      (node (ref "IC1") (pin "6") (pinfunction "AS_6") (pintype "output"))
      (node (ref "X1") (pin "B21") (pinfunction "B_B21") (pintype "passive"))
    )
    (net (code "160") (name "~{BERR}") (class "Default")
      (node (ref "IC1") (pin "24") (pinfunction "BERR_24") (pintype "input"))
      (node (ref "X1") (pin "B9") (pinfunction "B_B9") (pintype "passive"))
    )
    (net (code "161") (name "~{BGACK}") (class "Default")
      (node (ref "IC1") (pin "12") (pinfunction "BGACK_12") (pintype "input"))
      (node (ref "X1") (pin "B15") (pinfunction "B_B15") (pintype "passive"))
    )
    (net (code "162") (name "~{BG}") (class "Default")
      (node (ref "IC1") (pin "11") (pinfunction "BG_11") (pintype "output"))
      (node (ref "X1") (pin "B14") (pinfunction "B_B14") (pintype "passive"))
    )
    (net (code "163") (name "~{BR}") (class "Default")
      (node (ref "IC1") (pin "13") (pinfunction "BR_13") (pintype "input"))
      (node (ref "X1") (pin "B13") (pinfunction "B_B13") (pintype "passive"))
    )
    (net (code "164") (name "~{DTACK}") (class "Default")
      (node (ref "IC1") (pin "10") (pinfunction "DTACK_10") (pintype "input"))
      (node (ref "IC2") (pin "8") (pinfunction "O_8") (pintype "output"))
    )
    (net (code "165") (name "~{EXT_DTACK}") (class "Default")
      (node (ref "IC6") (pin "1") (pinfunction "I0_1") (pintype "input"))
      (node (ref "R8") (pin "2") (pinfunction "2_2") (pintype "passive"))
      (node (ref "X1") (pin "B28") (pinfunction "B_B28") (pintype "passive"))
    )
    (net (code "166") (name "~{EXT_IRQ}") (class "Default")
      (node (ref "IC5") (pin "1") (pinfunction "4_1") (pintype "input"))
      (node (ref "R4") (pin "2") (pinfunction "2_2") (pintype "passive"))
      (node (ref "X1") (pin "B17") (pinfunction "B_B17") (pintype "passive"))
    )
    (net (code "167") (name "~{HALT}") (class "Default")
      (node (ref "IC1") (pin "19") (pinfunction "HALT_19") (pintype "bidirectional"))
      (node (ref "IC7") (pin "10") (pinfunction "O_10") (pintype "output"))
      (node (ref "LED2") (pin "C") (pinfunction "C_C") (pintype "passive"))
      (node (ref "X1") (pin "B11") (pinfunction "B_B11") (pintype "passive"))
    )
    (net (code "168") (name "~{IPL0}") (class "Default")
      (node (ref "IC1") (pin "27") (pinfunction "IPL0_27") (pintype "input"))
      (node (ref "IC5") (pin "9") (pinfunction "A0_9") (pintype "output"))
    )
    (net (code "169") (name "~{IPL1}") (class "Default")
      (node (ref "IC1") (pin "26") (pinfunction "IPL1_26") (pintype "input"))
      (node (ref "IC5") (pin "7") (pinfunction "A1_7") (pintype "output"))
    )
    (net (code "170") (name "~{IPL2}") (class "Default")
      (node (ref "IC1") (pin "25") (pinfunction "IPL2_25") (pintype "input"))
      (node (ref "IC5") (pin "6") (pinfunction "A2_6") (pintype "output"))
    )
    (net (code "171") (name "~{LDS}") (class "Default")
      (node (ref "IC1") (pin "8") (pinfunction "LDS_8") (pintype "output"))
      (node (ref "X1") (pin "B24") (pinfunction "B_B24") (pintype "passive"))
    )
    (net (code "172") (name "~{NMI}") (class "Default")
      (node (ref "IC5") (pin "4") (pinfunction "7_4") (pintype "input"))
      (node (ref "IC7") (pin "12") (pinfunction "O_12") (pintype "output"))
      (node (ref "R7") (pin "2") (pinfunction "2_2") (pintype "passive"))
    )
    (net (code "173") (name "~{OE}") (class "Default")
      (node (ref "IC10") (pin "24") (pinfunction "~{OE}_24") (pintype "input"))
      (node (ref "IC11") (pin "24") (pinfunction "~{OE}_24") (pintype "input"))
      (node (ref "IC12") (pin "24") (pinfunction "~{OE}_24") (pintype "input"))
      (node (ref "IC13") (pin "24") (pinfunction "~{OE}_24") (pintype "input"))
      (node (ref "IC15") (pin "22") (pinfunction "~{OE}_22") (pintype "input"))
      (node (ref "IC2") (pin "2") (pinfunction "O_2") (pintype "output"))
      (node (ref "IC8") (pin "24") (pinfunction "~{OE}_24") (pintype "input"))
      (node (ref "IC9") (pin "24") (pinfunction "~{OE}_24") (pintype "input"))
    )
    (net (code "174") (name "~{REGION0}") (class "Default")
      (node (ref "IC12") (pin "22") (pinfunction "~{CS}_22") (pintype "input"))
      (node (ref "IC13") (pin "22") (pinfunction "~{CS}_22") (pintype "input"))
      (node (ref "IC3") (pin "1") (pinfunction "0_1") (pintype "output"))
      (node (ref "IC6") (pin "3") (pinfunction "I2_3") (pintype "input"))
    )
    (net (code "175") (name "~{REGION1}") (class "Default")
      (node (ref "IC10") (pin "22") (pinfunction "~{CE1}_22") (pintype "input"))
      (node (ref "IC11") (pin "22") (pinfunction "~{CE1}_22") (pintype "input"))
      (node (ref "IC3") (pin "2") (pinfunction "1_2") (pintype "output"))
      (node (ref "IC6") (pin "4") (pinfunction "I3_4") (pintype "input"))
      (node (ref "IC8") (pin "22") (pinfunction "~{CE1}_22") (pintype "input"))
      (node (ref "IC9") (pin "22") (pinfunction "~{CE1}_22") (pintype "input"))
    )
    (net (code "176") (name "~{REGION15}") (class "Default")
      (node (ref "IC2") (pin "3") (pinfunction "I_3") (pintype "input"))
      (node (ref "IC3") (pin "17") (pinfunction "15_17") (pintype "output"))
    )
    (net (code "177") (name "~{RESET}") (class "Default")
      (node (ref "IC1") (pin "20") (pinfunction "RESET_20") (pintype "bidirectional"))
      (node (ref "IC14") (pin "38") (pinfunction "~{RESET}_38") (pintype "input"))
      (node (ref "IC7") (pin "8") (pinfunction "O_8") (pintype "output"))
      (node (ref "LED3") (pin "C") (pinfunction "C_C") (pintype "passive"))
      (node (ref "X1") (pin "B10") (pinfunction "B_B10") (pintype "passive"))
    )
    (net (code "178") (name "~{RTC_CS}") (class "Default")
      (node (ref "IC15") (pin "20") (pinfunction "~{CS}_20") (pintype "input"))
      (node (ref "IC17") (pin "6") (pinfunction "O_6") (pintype "output"))
      (node (ref "IC6") (pin "5") (pinfunction "I4_5") (pintype "input"))
    )
    (net (code "179") (name "~{TIMER_IRQ}") (class "Default")
      (node (ref "IC5") (pin "3") (pinfunction "6_3") (pintype "input"))
      (node (ref "R6") (pin "2") (pinfunction "2_2") (pintype "passive"))
    )
    (net (code "180") (name "~{UDS}") (class "Default")
      (node (ref "IC1") (pin "7") (pinfunction "UDS_7") (pintype "output"))
      (node (ref "X1") (pin "B23") (pinfunction "B_B23") (pintype "passive"))
    )
    (net (code "181") (name "~{VPA}") (class "Default")
      (node (ref "IC1") (pin "23") (pinfunction "VPA_23") (pintype "input"))
      (node (ref "IC4") (pin "8") (pinfunction "O_8") (pintype "output"))
      (node (ref "X1") (pin "B12") (pinfunction "B_B12") (pintype "passive"))
    )
  )
)
